# ae302f.net
KiCad netlist of a schematic drawn in Altium Designer
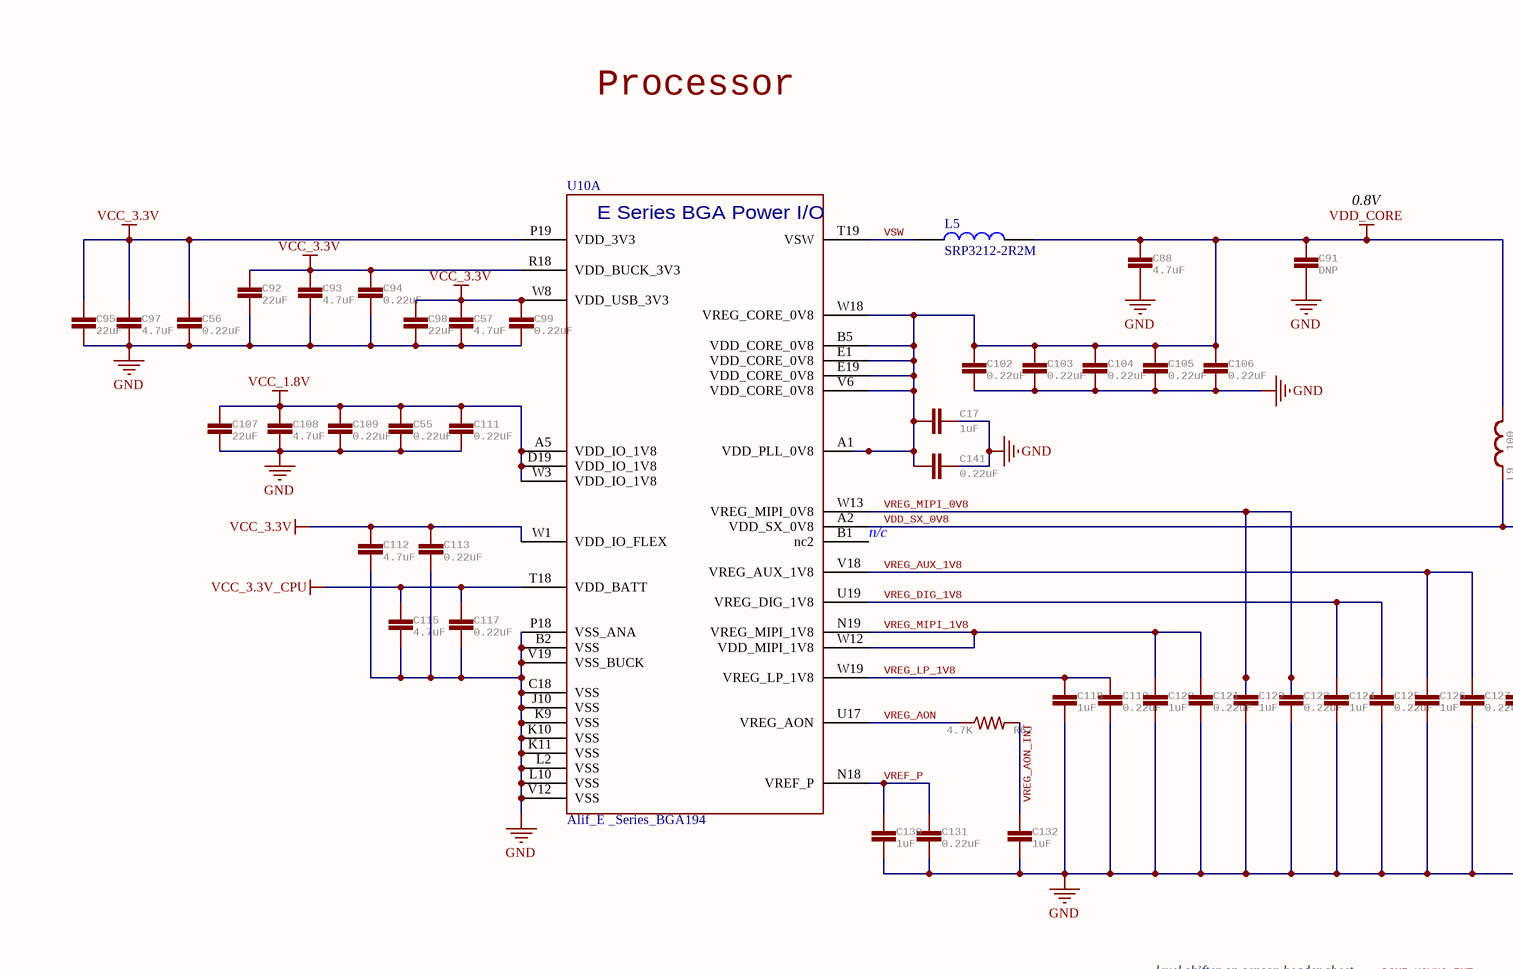
[diagram p0: ae302f.SchDoc, top left]
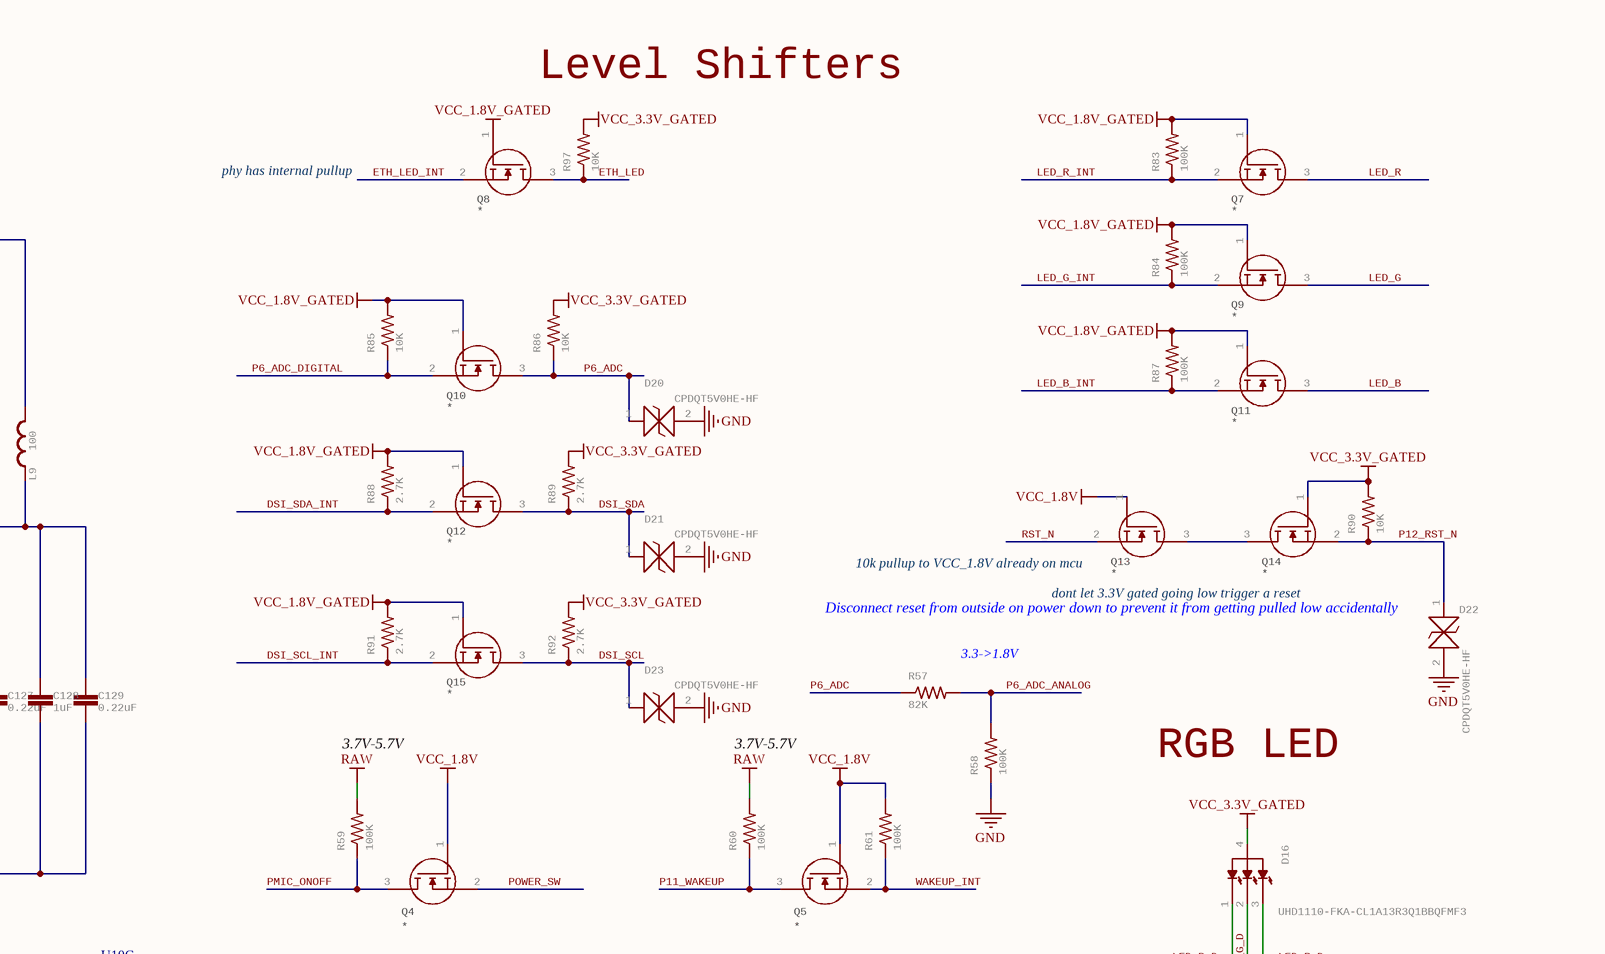
[diagram p1: ae302f.SchDoc, top right]
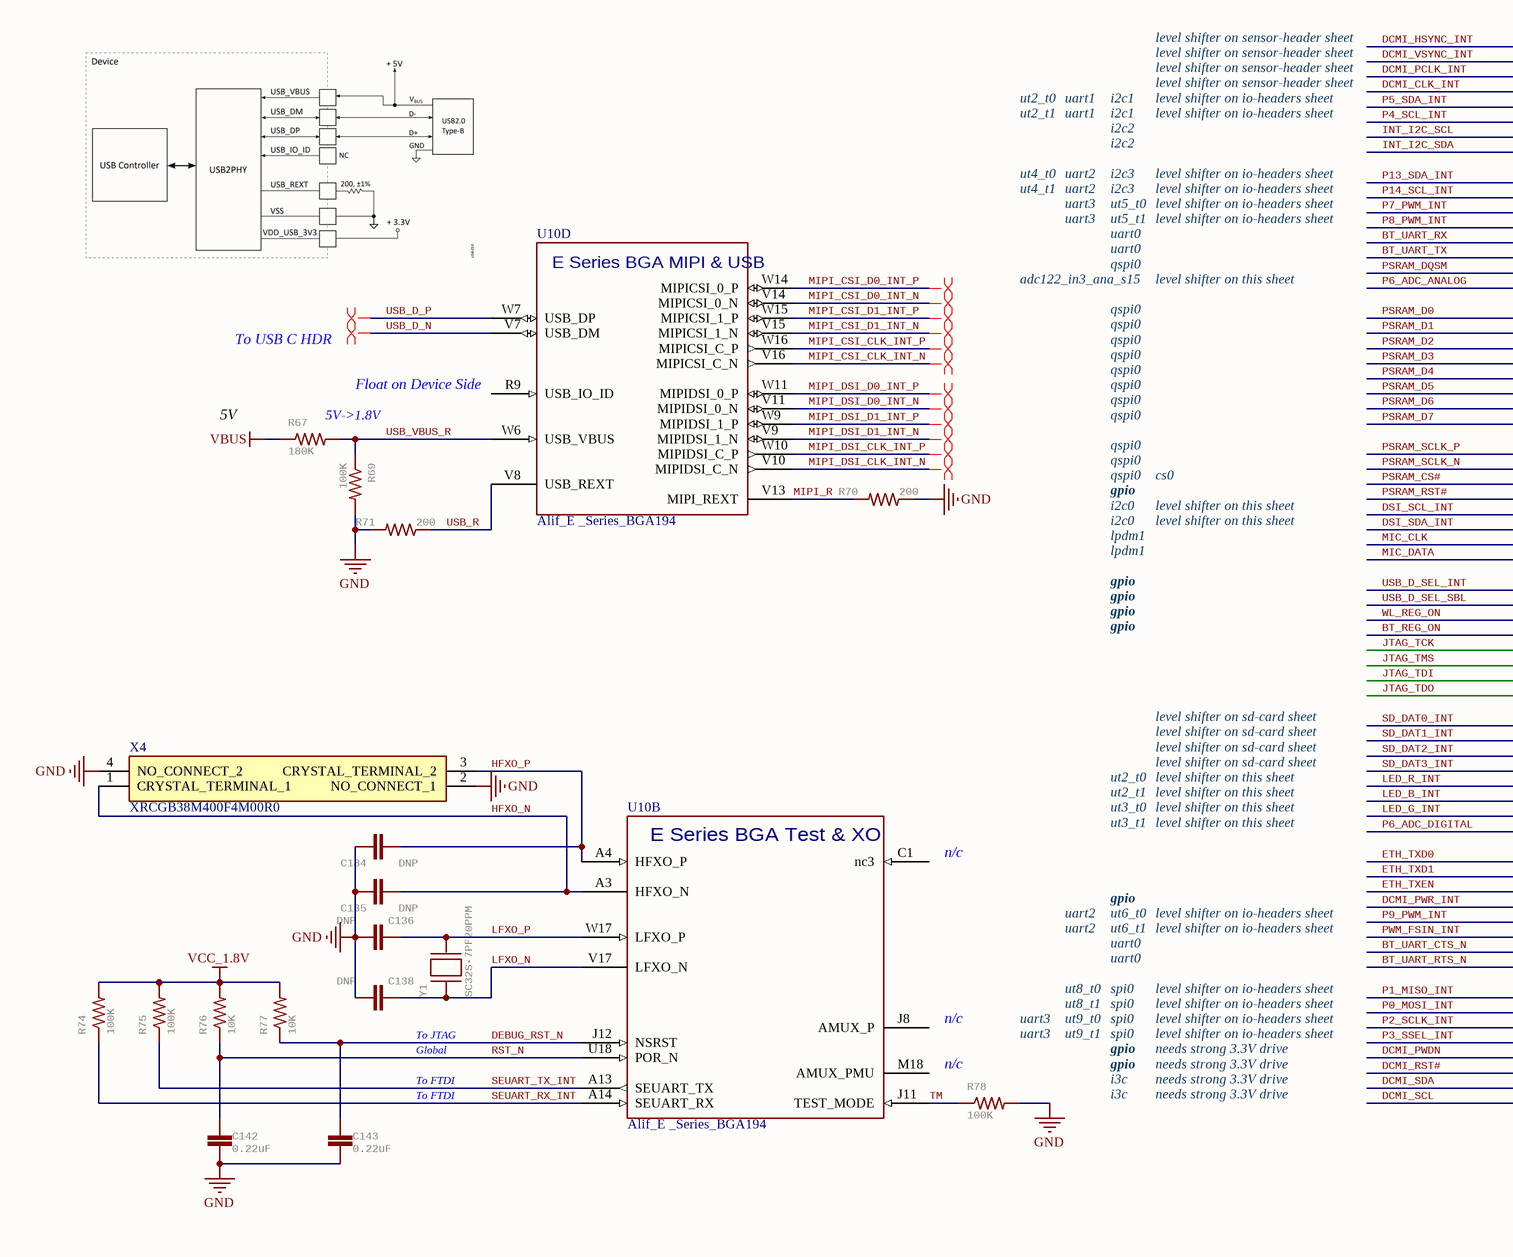
[diagram p2: ae302f.SchDoc, bottom left]
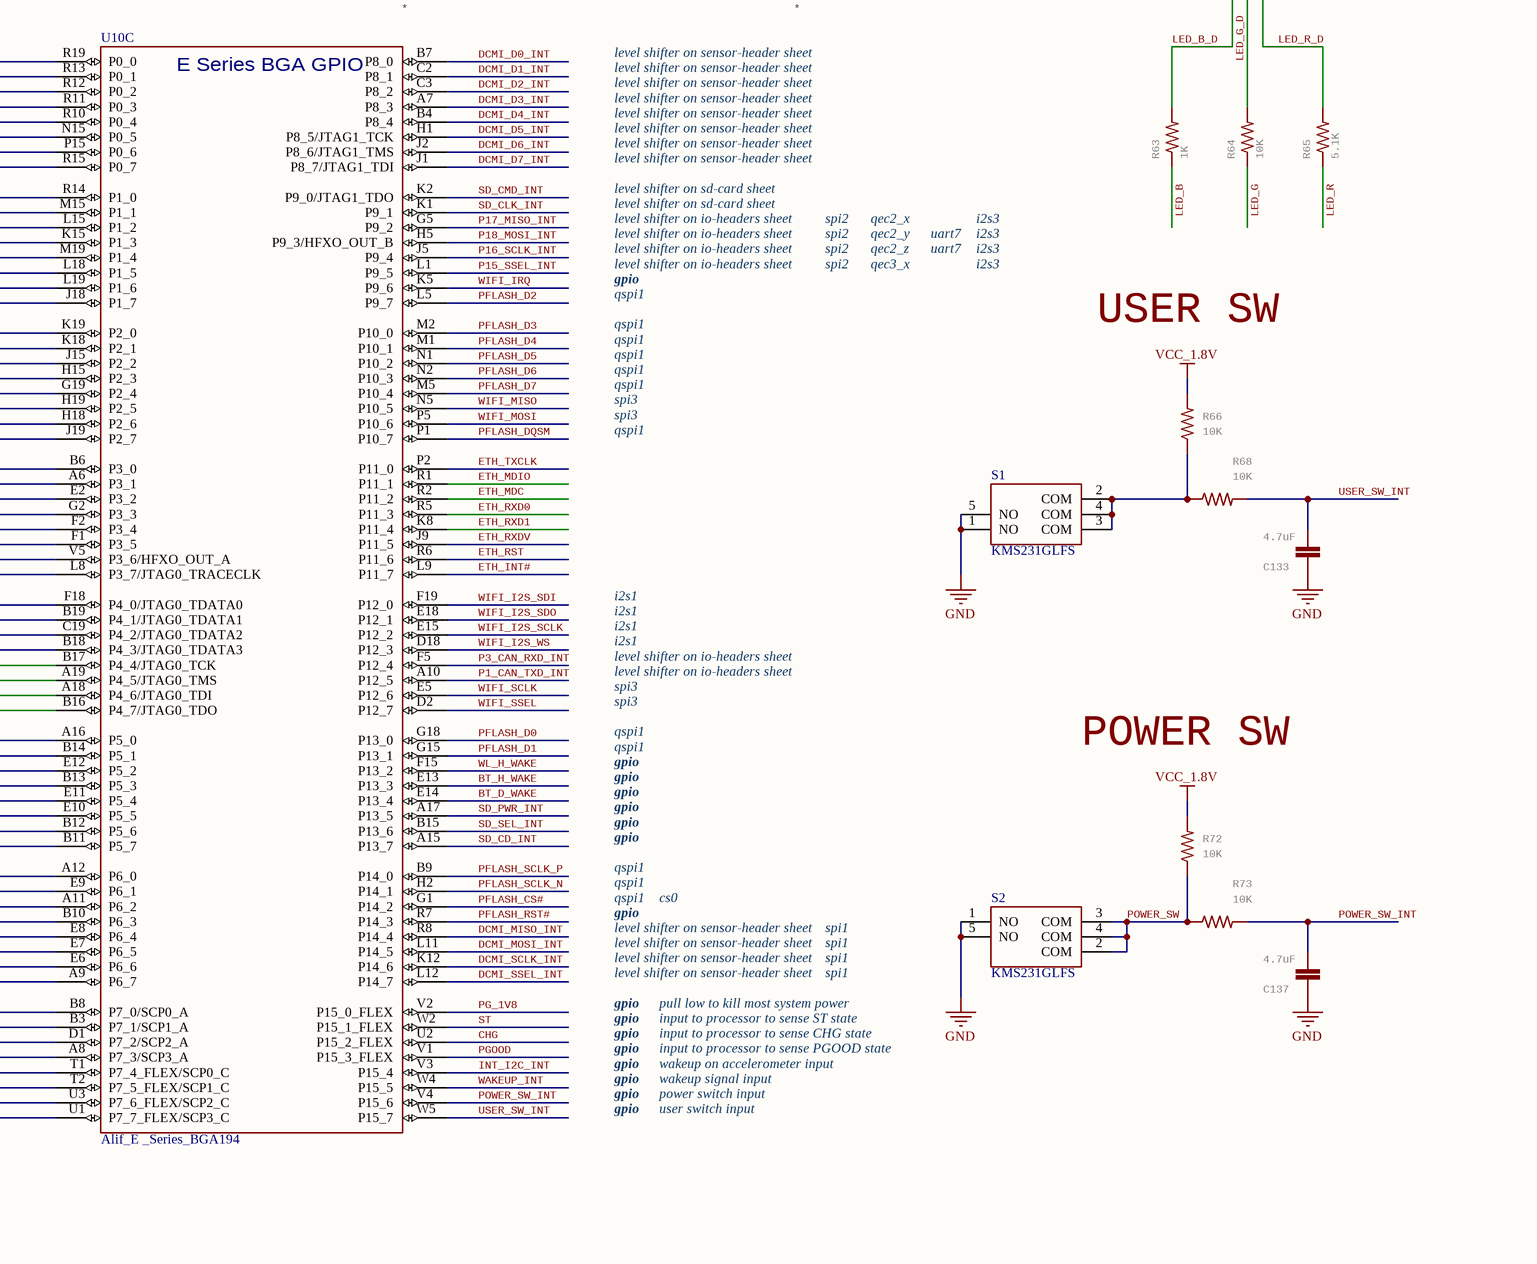
[diagram p3: ae302f.SchDoc, bottom right]

(export (version "E")
  (design (tool "Eeschema 10.0.6"))
  (components
    (comp (ref "C17")
      (value "1uF")
      (footprint "0402-CAP")
      (description "CapacitorStandard 0402 ceramic capacitor, and 0.1\" leaded capacitor.")
      (fields (field (name "MPN") "GRM155R61E105KA12J") (field (name "LIBRARYNAME") "sfe"))
      (libsource (lib "openmv-ae3") (part "CAP0402-CAP"))
    )
    (comp (ref "C55")
      (value "0.22uF")
      (footprint "C0201")
      (description "CAPACITOR, European symbol")
      (fields (field (name "MPN") "GRM033R60J224ME15D"))
      (libsource (lib "") (part "C-EUC0201_1"))
    )
    (comp (ref "C56")
      (value "0.22uF")
      (footprint "C0201")
      (description "CAPACITOR, European symbol")
      (fields (field (name "MPN") "GRM033R60J224ME15D"))
      (libsource (lib "") (part "C-EUC0201_1"))
    )
    (comp (ref "C57")
      (value "4.7uF")
      (footprint "0402-CAP")
      (description "CapacitorStandard 0603 ceramic capacitor, and 0.1\" leaded capacitor.")
      (fields (field (name "MPN") "JMK105BBJ475MV-F") (field (name "LIBRARYNAME") "sfe"))
      (libsource (lib "") (part "CAP0402-CAP_1"))
    )
    (comp (ref "C88")
      (value "4.7uF")
      (footprint "0402-CAP")
      (description "CapacitorStandard 0603 ceramic capacitor, and 0.1\" leaded capacitor.")
      (fields (field (name "MPN") "JMK105BBJ475MV-F") (field (name "LIBRARYNAME") "sfe"))
      (libsource (lib "") (part "CAP0402-CAP_1"))
    )
    (comp (ref "C91")
      (value "DNP")
      (footprint "0805")
      (libsource (lib "openmv-ae3") (part "22UF-0805-6.3V-20%"))
    )
    (comp (ref "C92")
      (value "22uF")
      (footprint "0805")
      (fields (field (name "MPN") "CL21A226MQQNNNE"))
      (libsource (lib "openmv-ae3") (part "22UF-0805-6.3V-20%"))
    )
    (comp (ref "C93")
      (value "4.7uF")
      (footprint "0402-CAP")
      (description "CapacitorStandard 0603 ceramic capacitor, and 0.1\" leaded capacitor.")
      (fields (field (name "MPN") "JMK105BBJ475MV-F") (field (name "LIBRARYNAME") "sfe"))
      (libsource (lib "") (part "CAP0402-CAP_1"))
    )
    (comp (ref "C94")
      (value "0.22uF")
      (footprint "C0201")
      (description "CAPACITOR, European symbol")
      (fields (field (name "MPN") "GRM033R60J224ME15D"))
      (libsource (lib "") (part "C-EUC0201_1"))
    )
    (comp (ref "C95")
      (value "22uF")
      (footprint "0805")
      (fields (field (name "MPN") "CL21A226MQQNNNE"))
      (libsource (lib "openmv-ae3") (part "22UF-0805-6.3V-20%"))
    )
    (comp (ref "C97")
      (value "4.7uF")
      (footprint "0402-CAP")
      (description "CapacitorStandard 0603 ceramic capacitor, and 0.1\" leaded capacitor.")
      (fields (field (name "MPN") "JMK105BBJ475MV-F") (field (name "LIBRARYNAME") "sfe"))
      (libsource (lib "") (part "CAP0402-CAP_1"))
    )
    (comp (ref "C98")
      (value "22uF")
      (footprint "0805")
      (fields (field (name "MPN") "CL21A226MQQNNNE"))
      (libsource (lib "openmv-ae3") (part "22UF-0805-6.3V-20%"))
    )
    (comp (ref "C99")
      (value "0.22uF")
      (footprint "C0201")
      (description "CAPACITOR, European symbol")
      (fields (field (name "MPN") "GRM033R60J224ME15D"))
      (libsource (lib "") (part "C-EUC0201_1"))
    )
    (comp (ref "C102")
      (value "0.22uF")
      (footprint "C0201")
      (description "CAPACITOR, European symbol")
      (fields (field (name "MPN") "GRM033R60J224ME15D"))
      (libsource (lib "") (part "C-EUC0201_1"))
    )
    (comp (ref "C103")
      (value "0.22uF")
      (footprint "C0201")
      (description "CAPACITOR, European symbol")
      (fields (field (name "MPN") "GRM033R60J224ME15D"))
      (libsource (lib "") (part "C-EUC0201_1"))
    )
    (comp (ref "C104")
      (value "0.22uF")
      (footprint "C0201")
      (description "CAPACITOR, European symbol")
      (fields (field (name "MPN") "GRM033R60J224ME15D"))
      (libsource (lib "") (part "C-EUC0201_1"))
    )
    (comp (ref "C105")
      (value "0.22uF")
      (footprint "C0201")
      (description "CAPACITOR, European symbol")
      (fields (field (name "MPN") "GRM033R60J224ME15D"))
      (libsource (lib "") (part "C-EUC0201_1"))
    )
    (comp (ref "C106")
      (value "0.22uF")
      (footprint "C0201")
      (description "CAPACITOR, European symbol")
      (fields (field (name "MPN") "GRM033R60J224ME15D"))
      (libsource (lib "") (part "C-EUC0201_1"))
    )
    (comp (ref "C107")
      (value "22uF")
      (footprint "0805")
      (fields (field (name "MPN") "CL21A226MQQNNNE"))
      (libsource (lib "openmv-ae3") (part "22UF-0805-6.3V-20%"))
    )
    (comp (ref "C108")
      (value "4.7uF")
      (footprint "0402-CAP")
      (description "CapacitorStandard 0603 ceramic capacitor, and 0.1\" leaded capacitor.")
      (fields (field (name "MPN") "JMK105BBJ475MV-F") (field (name "LIBRARYNAME") "sfe"))
      (libsource (lib "") (part "CAP0402-CAP_1"))
    )
    (comp (ref "C109")
      (value "0.22uF")
      (footprint "C0201")
      (description "CAPACITOR, European symbol")
      (fields (field (name "MPN") "GRM033R60J224ME15D"))
      (libsource (lib "") (part "C-EUC0201_1"))
    )
    (comp (ref "C111")
      (value "0.22uF")
      (footprint "C0201")
      (description "CAPACITOR, European symbol")
      (fields (field (name "MPN") "GRM033R60J224ME15D"))
      (libsource (lib "") (part "C-EUC0201_1"))
    )
    (comp (ref "C112")
      (value "4.7uF")
      (footprint "0402-CAP")
      (description "CapacitorStandard 0603 ceramic capacitor, and 0.1\" leaded capacitor.")
      (fields (field (name "MPN") "JMK105BBJ475MV-F") (field (name "LIBRARYNAME") "sfe"))
      (libsource (lib "") (part "CAP0402-CAP_1"))
    )
    (comp (ref "C113")
      (value "0.22uF")
      (footprint "C0201")
      (description "CAPACITOR, European symbol")
      (fields (field (name "MPN") "GRM033R60J224ME15D"))
      (libsource (lib "") (part "C-EUC0201_1"))
    )
    (comp (ref "C115")
      (value "4.7uF")
      (footprint "0402-CAP")
      (description "CapacitorStandard 0603 ceramic capacitor, and 0.1\" leaded capacitor.")
      (fields (field (name "MPN") "JMK105BBJ475MV-F") (field (name "LIBRARYNAME") "sfe"))
      (libsource (lib "") (part "CAP0402-CAP_1"))
    )
    (comp (ref "C117")
      (value "0.22uF")
      (footprint "C0201")
      (description "CAPACITOR, European symbol")
      (fields (field (name "MPN") "GRM033R60J224ME15D"))
      (libsource (lib "") (part "C-EUC0201_1"))
    )
    (comp (ref "C118")
      (value "1uF")
      (footprint "0402-CAP")
      (description "CapacitorStandard 0402 ceramic capacitor, and 0.1\" leaded capacitor.")
      (fields (field (name "MPN") "GRM155R61E105KA12J") (field (name "LIBRARYNAME") "sfe"))
      (libsource (lib "") (part "CAP0402-CAP_1"))
    )
    (comp (ref "C119")
      (value "0.22uF")
      (footprint "C0201")
      (description "CAPACITOR, European symbol")
      (fields (field (name "MPN") "GRM033R60J224ME15D"))
      (libsource (lib "") (part "C-EUC0201_1"))
    )
    (comp (ref "C120")
      (value "1uF")
      (footprint "0402-CAP")
      (description "CapacitorStandard 0402 ceramic capacitor, and 0.1\" leaded capacitor.")
      (fields (field (name "MPN") "GRM155R61E105KA12J") (field (name "LIBRARYNAME") "sfe"))
      (libsource (lib "") (part "CAP0402-CAP_1"))
    )
    (comp (ref "C121")
      (value "0.22uF")
      (footprint "C0201")
      (description "CAPACITOR, European symbol")
      (fields (field (name "MPN") "GRM033R60J224ME15D"))
      (libsource (lib "") (part "C-EUC0201_1"))
    )
    (comp (ref "C122")
      (value "1uF")
      (footprint "0402-CAP")
      (description "CapacitorStandard 0402 ceramic capacitor, and 0.1\" leaded capacitor.")
      (fields (field (name "MPN") "GRM155R61E105KA12J") (field (name "LIBRARYNAME") "sfe"))
      (libsource (lib "") (part "CAP0402-CAP_1"))
    )
    (comp (ref "C123")
      (value "0.22uF")
      (footprint "C0201")
      (description "CAPACITOR, European symbol")
      (fields (field (name "MPN") "GRM033R60J224ME15D"))
      (libsource (lib "") (part "C-EUC0201_1"))
    )
    (comp (ref "C124")
      (value "1uF")
      (footprint "0402-CAP")
      (description "CapacitorStandard 0402 ceramic capacitor, and 0.1\" leaded capacitor.")
      (fields (field (name "MPN") "GRM155R61E105KA12J") (field (name "LIBRARYNAME") "sfe"))
      (libsource (lib "") (part "CAP0402-CAP_1"))
    )
    (comp (ref "C125")
      (value "0.22uF")
      (footprint "C0201")
      (description "CAPACITOR, European symbol")
      (fields (field (name "MPN") "GRM033R60J224ME15D"))
      (libsource (lib "") (part "C-EUC0201_1"))
    )
    (comp (ref "C126")
      (value "1uF")
      (footprint "0402-CAP")
      (description "CapacitorStandard 0402 ceramic capacitor, and 0.1\" leaded capacitor.")
      (fields (field (name "MPN") "GRM155R61E105KA12J") (field (name "LIBRARYNAME") "sfe"))
      (libsource (lib "") (part "CAP0402-CAP_1"))
    )
    (comp (ref "C127")
      (value "0.22uF")
      (footprint "C0201")
      (description "CAPACITOR, European symbol")
      (fields (field (name "MPN") "GRM033R60J224ME15D"))
      (libsource (lib "") (part "C-EUC0201_2"))
    )
    (comp (ref "C128")
      (value "1uF")
      (footprint "0402-CAP")
      (description "CapacitorStandard 0402 ceramic capacitor, and 0.1\" leaded capacitor.")
      (fields (field (name "MPN") "GRM155R61E105KA12J") (field (name "LIBRARYNAME") "sfe"))
      (libsource (lib "") (part "CAP0402-CAP_1"))
    )
    (comp (ref "C129")
      (value "0.22uF")
      (footprint "C0201")
      (description "CAPACITOR, European symbol")
      (fields (field (name "MPN") "GRM033R60J224ME15D"))
      (libsource (lib "") (part "C-EUC0201_1"))
    )
    (comp (ref "C130")
      (value "1uF")
      (footprint "0402-CAP")
      (description "CapacitorStandard 0402 ceramic capacitor, and 0.1\" leaded capacitor.")
      (fields (field (name "MPN") "GRM155R61E105KA12J") (field (name "LIBRARYNAME") "sfe"))
      (libsource (lib "") (part "CAP0402-CAP_1"))
    )
    (comp (ref "C131")
      (value "0.22uF")
      (footprint "C0201")
      (description "CAPACITOR, European symbol")
      (fields (field (name "MPN") "GRM033R60J224ME15D"))
      (libsource (lib "") (part "C-EUC0201_1"))
    )
    (comp (ref "C132")
      (value "1uF")
      (footprint "0402-CAP")
      (description "CapacitorStandard 0402 ceramic capacitor, and 0.1\" leaded capacitor.")
      (fields (field (name "MPN") "GRM155R61E105KA12J") (field (name "LIBRARYNAME") "sfe"))
      (libsource (lib "") (part "CAP0402-CAP_1"))
    )
    (comp (ref "C133")
      (value "4.7uF")
      (footprint "0402-CAP")
      (description "CapacitorStandard 0603 ceramic capacitor, and 0.1\" leaded capacitor.")
      (fields (field (name "MPN") "JMK105BBJ475MV-F") (field (name "LIBRARYNAME") "sfe"))
      (libsource (lib "") (part "CAP0402-CAP_2"))
    )
    (comp (ref "C134")
      (value "DNP")
      (footprint "C0201")
      (description "CAPACITOR, European symbol")
      (libsource (lib "openmv-ae3") (part "C-EUC0201"))
    )
    (comp (ref "C135")
      (value "DNP")
      (footprint "C0201")
      (description "CAPACITOR, European symbol")
      (libsource (lib "openmv-ae3") (part "C-EUC0201"))
    )
    (comp (ref "C136")
      (value "DNP")
      (footprint "C0201")
      (description "CAPACITOR, European symbol")
      (libsource (lib "") (part "C-EUC0201_3"))
    )
    (comp (ref "C137")
      (value "4.7uF")
      (footprint "0402-CAP")
      (description "CapacitorStandard 0603 ceramic capacitor, and 0.1\" leaded capacitor.")
      (fields (field (name "MPN") "JMK105BBJ475MV-F") (field (name "LIBRARYNAME") "sfe"))
      (libsource (lib "") (part "CAP0402-CAP_2"))
    )
    (comp (ref "C138")
      (value "DNP")
      (footprint "C0201")
      (description "CAPACITOR, European symbol")
      (libsource (lib "") (part "C-EUC0201_3"))
    )
    (comp (ref "C141")
      (value "0.22uF")
      (footprint "C0201")
      (description "CAPACITOR, European symbol")
      (fields (field (name "MPN") "GRM033R60J224ME15D"))
      (libsource (lib "") (part "C-EUC0201_3"))
    )
    (comp (ref "C142")
      (value "0.22uF")
      (footprint "C0201")
      (description "CAPACITOR, European symbol")
      (fields (field (name "MPN") "GRM033R60J224ME15D"))
      (libsource (lib "") (part "C-EUC0201_1"))
    )
    (comp (ref "C143")
      (value "0.22uF")
      (footprint "C0201")
      (description "CAPACITOR, European symbol")
      (fields (field (name "MPN") "GRM033R60J224ME15D"))
      (libsource (lib "") (part "C-EUC0201_1"))
    )
    (comp (ref "D16")
      (value "UHD1110-FKA-CL1A13R3Q1BBQFMF3")
      (footprint "LED_UHD1110-FKA-CL1A13R3Q1BBQFMF3")
      (description "LED RGB SMD, SIZE 1 X 1 mm Check availability")
      (fields (field (name "MF") "Cree Inc.") (field (name "MPN") "UHD1110-FKA-CL1A13r3q1BBQFMF3"))
      (libsource (lib "openmv-ae3") (part "UHD1110-FKA-CL1A13R3Q1BBQFMF3"))
    )
    (comp (ref "D20")
      (value "CPDQT5V0HE-HF")
      (footprint "CPDQT5V0HEHF")
      (description "ESD Suppressors / TVS Diodes DIODE ESD 5VWM 65W 0402/SOD-923F   Source:  Datasheet")
      (fields (field (name "MOUSER_PART_NUMBER") "MOUSER_PART_NUMBER"))
      (libsource (lib "openmv-ae3") (part "CPDQT5V0HE-HF"))
    )
    (comp (ref "D21")
      (value "CPDQT5V0HE-HF")
      (footprint "CPDQT5V0HEHF")
      (description "ESD Suppressors / TVS Diodes DIODE ESD 5VWM 65W 0402/SOD-923F   Source:  Datasheet")
      (fields (field (name "MOUSER_PART_NUMBER") "MOUSER_PART_NUMBER"))
      (libsource (lib "openmv-ae3") (part "CPDQT5V0HE-HF"))
    )
    (comp (ref "D22")
      (value "CPDQT5V0HE-HF")
      (footprint "CPDQT5V0HEHF")
      (description "ESD Suppressors / TVS Diodes DIODE ESD 5VWM 65W 0402/SOD-923F   Source:  Datasheet")
      (fields (field (name "MOUSER_PART_NUMBER") "MOUSER_PART_NUMBER"))
      (libsource (lib "openmv-ae3") (part "CPDQT5V0HE-HF"))
    )
    (comp (ref "D23")
      (value "CPDQT5V0HE-HF")
      (footprint "CPDQT5V0HEHF")
      (description "ESD Suppressors / TVS Diodes DIODE ESD 5VWM 65W 0402/SOD-923F   Source:  Datasheet")
      (fields (field (name "MOUSER_PART_NUMBER") "MOUSER_PART_NUMBER"))
      (libsource (lib "openmv-ae3") (part "CPDQT5V0HE-HF"))
    )
    (comp (ref "L5")
      (value "SRP3212-2R2M")
      (footprint "IND3225X100N")
      (description "Ind,3.2x2.5x1mm,2.2uH?20%,4A,shd")
      (fields (field (name "MOUSER PART NUMBER") "652-SRP3212-2R2M"))
      (libsource (lib "openmv-ae3") (part "SRP3212-2R2M"))
    )
    (comp (ref "L9")
      (value "100")
      (footprint "C0402")
      (fields (field (name "MPN") "MFBM1V1005-101-R") (field (name "LIBRARYNAME") "sfe"))
      (libsource (lib "openmv-ae3") (part "INDUCTOR0402"))
    )
    (comp (ref "Q4")
      (value "NMOS")
      (footprint "DFN1006")
      (fields (field (name "MPN") "*"))
      (libsource (lib "openmv-ae3") (part "NMOS"))
    )
    (comp (ref "Q5")
      (value "NMOS")
      (footprint "DFN1006")
      (fields (field (name "MPN") "*"))
      (libsource (lib "openmv-ae3") (part "NMOS"))
    )
    (comp (ref "Q7")
      (value "NMOS")
      (footprint "DFN1006")
      (fields (field (name "MPN") "*"))
      (libsource (lib "openmv-ae3") (part "NMOS"))
    )
    (comp (ref "Q8")
      (value "NMOS")
      (footprint "DFN1006")
      (fields (field (name "MPN") "*"))
      (libsource (lib "openmv-ae3") (part "NMOS"))
    )
    (comp (ref "Q9")
      (value "NMOS")
      (footprint "DFN1006")
      (fields (field (name "MPN") "*"))
      (libsource (lib "openmv-ae3") (part "NMOS"))
    )
    (comp (ref "Q10")
      (value "NMOS")
      (footprint "DFN1006")
      (fields (field (name "MPN") "*"))
      (libsource (lib "openmv-ae3") (part "NMOS"))
    )
    (comp (ref "Q11")
      (value "NMOS")
      (footprint "DFN1006")
      (fields (field (name "MPN") "*"))
      (libsource (lib "openmv-ae3") (part "NMOS"))
    )
    (comp (ref "Q12")
      (value "NMOS")
      (footprint "DFN1006")
      (fields (field (name "MPN") "*"))
      (libsource (lib "openmv-ae3") (part "NMOS"))
    )
    (comp (ref "Q13")
      (value "NMOS")
      (footprint "DFN1006")
      (fields (field (name "MPN") "*"))
      (libsource (lib "openmv-ae3") (part "NMOS"))
    )
    (comp (ref "Q14")
      (value "NMOS")
      (footprint "DFN1006")
      (fields (field (name "MPN") "*"))
      (libsource (lib "openmv-ae3") (part "NMOS"))
    )
    (comp (ref "Q15")
      (value "NMOS")
      (footprint "DFN1006")
      (fields (field (name "MPN") "*"))
      (libsource (lib "openmv-ae3") (part "NMOS"))
    )
    (comp (ref "R57")
      (value "82K")
      (footprint "R0201")
      (fields (field (name "LIBRARYNAME") "sfe"))
      (libsource (lib "openmv-ae3") (part "RESISTOR0402-RES"))
    )
    (comp (ref "R58")
      (value "100K")
      (footprint "R0201")
      (fields (field (name "LIBRARYNAME") "sfe"))
      (libsource (lib "openmv-ae3") (part "RESISTOR0402-RES"))
    )
    (comp (ref "R59")
      (value "100K")
      (footprint "0402-RES")
      (description "ResistorBasic schematic elements and footprints for 0603, 1206, and PTH resistors.")
      (fields (field (name "MPN") "AC0402FR-07100KL") (field (name "LIBRARYNAME") "sfe"))
      (libsource (lib "openmv-ae3") (part "RESISTOR0402-RES"))
    )
    (comp (ref "R60")
      (value "100K")
      (footprint "R0201")
      (fields (field (name "LIBRARYNAME") "sfe"))
      (libsource (lib "openmv-ae3") (part "RESISTOR0402-RES"))
    )
    (comp (ref "R61")
      (value "100K")
      (footprint "R0201")
      (fields (field (name "LIBRARYNAME") "sfe"))
      (libsource (lib "openmv-ae3") (part "RESISTOR0402-RES"))
    )
    (comp (ref "R62")
      (value "4.7K")
      (footprint "0402-RES")
      (description "ResistorBasic schematic elements and footprints for 0603, 1206, and PTH resistors.")
      (fields (field (name "MPN") "RT0402FRE074K7L") (field (name "LIBRARYNAME") "sfe"))
      (libsource (lib "openmv-ae3") (part "RESISTOR0402-RES"))
    )
    (comp (ref "R63")
      (value "1K")
      (footprint "R0201")
      (description "ResistorBasic schematic elements and footprints for 0603, 1206, and PTH resistors.")
      (fields (field (name "LIBRARYNAME") "sfe"))
      (libsource (lib "openmv-ae3") (part "RESISTOR0402-RES"))
    )
    (comp (ref "R64")
      (value "10K")
      (footprint "R0201")
      (description "ResistorBasic schematic elements and footprints for 0603, 1206, and PTH resistors.")
      (fields (field (name "LIBRARYNAME") "sfe"))
      (libsource (lib "openmv-ae3") (part "RESISTOR0402-RES"))
    )
    (comp (ref "R65")
      (value "5.1K")
      (footprint "R0201")
      (description "ResistorBasic schematic elements and footprints for 0603, 1206, and PTH resistors.")
      (fields (field (name "LIBRARYNAME") "sfe"))
      (libsource (lib "openmv-ae3") (part "RESISTOR0402-RES"))
    )
    (comp (ref "R66")
      (value "10K")
      (footprint "0402-RES")
      (description "ResistorBasic schematic elements and footprints for 0603, 1206, and PTH resistors.")
      (fields (field (name "MPN") "AC0402FR-1310K") (field (name "LIBRARYNAME") "sfe"))
      (libsource (lib "openmv-ae3") (part "RESISTOR0402-RES"))
    )
    (comp (ref "R67")
      (value "180K")
      (footprint "R0201")
      (fields (field (name "LIBRARYNAME") "sfe"))
      (libsource (lib "openmv-ae3") (part "RESISTOR0402-RES"))
    )
    (comp (ref "R68")
      (value "10K")
      (footprint "0402-RES")
      (description "ResistorBasic schematic elements and footprints for 0603, 1206, and PTH resistors.")
      (fields (field (name "MPN") "AC0402FR-1310K") (field (name "LIBRARYNAME") "sfe"))
      (libsource (lib "openmv-ae3") (part "RESISTOR0402-RES"))
    )
    (comp (ref "R69")
      (value "100K")
      (footprint "R0201")
      (fields (field (name "LIBRARYNAME") "sfe"))
      (libsource (lib "openmv-ae3") (part "RESISTOR0402-RES"))
    )
    (comp (ref "R70")
      (value "200")
      (footprint "R0201")
      (fields (field (name "LIBRARYNAME") "sfe"))
      (libsource (lib "openmv-ae3") (part "RESISTOR0402-RES"))
    )
    (comp (ref "R71")
      (value "200")
      (footprint "R0201")
      (fields (field (name "LIBRARYNAME") "sfe"))
      (libsource (lib "openmv-ae3") (part "RESISTOR0402-RES"))
    )
    (comp (ref "R72")
      (value "10K")
      (footprint "0402-RES")
      (description "ResistorBasic schematic elements and footprints for 0603, 1206, and PTH resistors.")
      (fields (field (name "MPN") "AC0402FR-1310K") (field (name "LIBRARYNAME") "sfe"))
      (libsource (lib "openmv-ae3") (part "RESISTOR0402-RES"))
    )
    (comp (ref "R73")
      (value "10K")
      (footprint "0402-RES")
      (description "ResistorBasic schematic elements and footprints for 0603, 1206, and PTH resistors.")
      (fields (field (name "MPN") "AC0402FR-1310K") (field (name "LIBRARYNAME") "sfe"))
      (libsource (lib "openmv-ae3") (part "RESISTOR0402-RES"))
    )
    (comp (ref "R74")
      (value "100K")
      (footprint "R0201")
      (fields (field (name "LIBRARYNAME") "sfe"))
      (libsource (lib "openmv-ae3") (part "RESISTOR0402-RES"))
    )
    (comp (ref "R75")
      (value "100K")
      (footprint "R0201")
      (fields (field (name "LIBRARYNAME") "sfe"))
      (libsource (lib "openmv-ae3") (part "RESISTOR0402-RES"))
    )
    (comp (ref "R76")
      (value "10K")
      (footprint "R0201")
      (fields (field (name "LIBRARYNAME") "sfe"))
      (libsource (lib "openmv-ae3") (part "RESISTOR0402-RES"))
    )
    (comp (ref "R77")
      (value "10K")
      (footprint "R0201")
      (fields (field (name "LIBRARYNAME") "sfe"))
      (libsource (lib "openmv-ae3") (part "RESISTOR0402-RES"))
    )
    (comp (ref "R78")
      (value "100K")
      (footprint "r0201")
      (fields (field (name "LIBRARYNAME") "sfe"))
      (libsource (lib "openmv-ae3") (part "RESISTOR0402-RES"))
    )
    (comp (ref "R83")
      (value "100K")
      (footprint "R0201")
      (fields (field (name "LIBRARYNAME") "sfe"))
      (libsource (lib "openmv-ae3") (part "RESISTOR0402-RES"))
    )
    (comp (ref "R84")
      (value "100K")
      (footprint "R0201")
      (fields (field (name "LIBRARYNAME") "sfe"))
      (libsource (lib "openmv-ae3") (part "RESISTOR0402-RES"))
    )
    (comp (ref "R85")
      (value "10K")
      (footprint "R0201")
      (description "ResistorBasic schematic elements and footprints for 0603, 1206, and PTH resistors.")
      (fields (field (name "LIBRARYNAME") "sfe"))
      (libsource (lib "openmv-ae3") (part "RESISTOR0402-RES"))
    )
    (comp (ref "R86")
      (value "10K")
      (footprint "R0201")
      (description "ResistorBasic schematic elements and footprints for 0603, 1206, and PTH resistors.")
      (fields (field (name "LIBRARYNAME") "sfe"))
      (libsource (lib "openmv-ae3") (part "RESISTOR0402-RES"))
    )
    (comp (ref "R87")
      (value "100K")
      (footprint "R0201")
      (fields (field (name "LIBRARYNAME") "sfe"))
      (libsource (lib "openmv-ae3") (part "RESISTOR0402-RES"))
    )
    (comp (ref "R88")
      (value "2.7K")
      (footprint "R0201")
      (fields (field (name "LIBRARYNAME") "sfe"))
      (libsource (lib "openmv-ae3") (part "RESISTOR0402-RES"))
    )
    (comp (ref "R89")
      (value "2.7K")
      (footprint "R0201")
      (fields (field (name "LIBRARYNAME") "sfe"))
      (libsource (lib "openmv-ae3") (part "RESISTOR0402-RES"))
    )
    (comp (ref "R90")
      (value "10K")
      (footprint "R0201")
      (description "ResistorBasic schematic elements and footprints for 0603, 1206, and PTH resistors.")
      (fields (field (name "LIBRARYNAME") "sfe"))
      (libsource (lib "openmv-ae3") (part "RESISTOR0402-RES"))
    )
    (comp (ref "R91")
      (value "2.7K")
      (footprint "R0201")
      (fields (field (name "LIBRARYNAME") "sfe"))
      (libsource (lib "openmv-ae3") (part "RESISTOR0402-RES"))
    )
    (comp (ref "R92")
      (value "2.7K")
      (footprint "R0201")
      (fields (field (name "LIBRARYNAME") "sfe"))
      (libsource (lib "openmv-ae3") (part "RESISTOR0402-RES"))
    )
    (comp (ref "R97")
      (value "10K")
      (footprint "R0201")
      (description "ResistorBasic schematic elements and footprints for 0603, 1206, and PTH resistors.")
      (fields (field (name "LIBRARYNAME") "sfe"))
      (libsource (lib "openmv-ae3") (part "RESISTOR0402-RES"))
    )
    (comp (ref "S1") (value "KMS231GLFS") (footprint "KMS231GLFS") (libsource (lib "") (part "KMS231GLFS_1")))
    (comp (ref "S2")
      (value "KMS231GLFS")
      (footprint "KMS231GLFS")
      (libsource (lib "openmv-ae3") (part "KMS231GLFS"))
    )
    (comp (ref "U10")
      (value "Alif_E _Series_BGA194")
      (footprint "BGA194 _CENTERED")
      (description "IC,Alif E7 MCU, Rev B silicon,BGA194")
      (fields (field (name "PART NUMBER") "AE302F80F55D5LE"))
      (libsource (lib "openmv-ae3") (part "E7_Bx_BGA_194_noGNSS"))
    )
    (comp (ref "X4")
      (value "XRCGB38M400F4M00R0")
      (footprint "XTAL_2016")
      (description "2.0X1.6X0.65MM 38.4MHZ CRYSTAL")
      (libsource (lib "openmv-ae3") (part "XRCGB38M400F4M00R0"))
    )
    (comp (ref "Y1")
      (value "SC32S-7PF20PPM")
      (footprint "XTAL_ABS07-32.768KHZ-7-T")
      (description "Check availability")
      (fields (field (name "MF") "Abracon") (field (name "MP") "ABS07-32.768KHZ-7-T"))
      (libsource (lib "openmv-ae3") (part "ABS07-32.768KHZ-7-T"))
    )
  )
  (nets
    (net (code "1") (name "/BT_D_WAKE") (class "Default")
      (node (ref "U10") (pin "E14") (pinfunction "P13_4_E14") (pintype "bidirectional"))
    )
    (net (code "2") (name "/BT_H_WAKE") (class "Default")
      (node (ref "U10") (pin "E13") (pinfunction "P13_3_E13") (pintype "bidirectional"))
    )
    (net (code "3") (name "/BT_REG_ON") (class "Default")
      (node (ref "U10") (pin "B18") (pinfunction "P4_3/JTAG0_TDATA3_B18") (pintype "bidirectional"))
    )
    (net (code "4") (name "/BT_UART_CTS_N") (class "Default")
      (node (ref "U10") (pin "E6") (pinfunction "P6_6_E6") (pintype "bidirectional"))
    )
    (net (code "5") (name "/BT_UART_RTS_N") (class "Default")
      (node (ref "U10") (pin "A9") (pinfunction "P6_7_A9") (pintype "bidirectional"))
    )
    (net (code "6") (name "/BT_UART_RX") (class "Default")
      (node (ref "U10") (pin "M19") (pinfunction "P1_4_M19") (pintype "bidirectional"))
    )
    (net (code "7") (name "/BT_UART_TX") (class "Default")
      (node (ref "U10") (pin "L18") (pinfunction "P1_5_L18") (pintype "bidirectional"))
    )
    (net (code "8") (name "/CHG") (class "Default")
      (node (ref "U10") (pin "U2") (pinfunction "P15_2_FLEX_U2") (pintype "bidirectional"))
    )
    (net (code "9") (name "/DCMI_CLK_INT") (class "Default")
      (node (ref "U10") (pin "R11") (pinfunction "P0_3_R11") (pintype "bidirectional"))
    )
    (net (code "10") (name "/DCMI_D0_INT") (class "Default")
      (node (ref "U10") (pin "B7") (pinfunction "P8_0_B7") (pintype "bidirectional"))
    )
    (net (code "11") (name "/DCMI_D1_INT") (class "Default")
      (node (ref "U10") (pin "C2") (pinfunction "P8_1_C2") (pintype "bidirectional"))
    )
    (net (code "12") (name "/DCMI_D2_INT") (class "Default")
      (node (ref "U10") (pin "C3") (pinfunction "P8_2_C3") (pintype "bidirectional"))
    )
    (net (code "13") (name "/DCMI_D3_INT") (class "Default")
      (node (ref "U10") (pin "A7") (pinfunction "P8_3_A7") (pintype "bidirectional"))
    )
    (net (code "14") (name "/DCMI_D4_INT") (class "Default")
      (node (ref "U10") (pin "B4") (pinfunction "P8_4_B4") (pintype "bidirectional"))
    )
    (net (code "15") (name "/DCMI_D5_INT") (class "Default")
      (node (ref "U10") (pin "H1") (pinfunction "P8_5/JTAG1_TCK_H1") (pintype "bidirectional"))
    )
    (net (code "16") (name "/DCMI_D6_INT") (class "Default")
      (node (ref "U10") (pin "J2") (pinfunction "P8_6/JTAG1_TMS_J2") (pintype "bidirectional"))
    )
    (net (code "17") (name "/DCMI_D7_INT") (class "Default")
      (node (ref "U10") (pin "J1") (pinfunction "P8_7/JTAG1_TDI_J1") (pintype "bidirectional"))
    )
    (net (code "18") (name "/DCMI_HSYNC_INT") (class "Default")
      (node (ref "U10") (pin "R19") (pinfunction "P0_0_R19") (pintype "bidirectional"))
    )
    (net (code "19") (name "/DCMI_MISO_INT") (class "Default")
      (node (ref "U10") (pin "R8") (pinfunction "P14_4_R8") (pintype "bidirectional"))
    )
    (net (code "20") (name "/DCMI_MOSI_INT") (class "Default")
      (node (ref "U10") (pin "L11") (pinfunction "P14_5_L11") (pintype "bidirectional"))
    )
    (net (code "21") (name "/DCMI_PCLK_INT") (class "Default")
      (node (ref "U10") (pin "R12") (pinfunction "P0_2_R12") (pintype "bidirectional"))
    )
    (net (code "22") (name "/DCMI_PWDN") (class "Default")
      (node (ref "U10") (pin "T1") (pinfunction "P7_4_FLEX/SCP0_C_T1") (pintype "bidirectional"))
    )
    (net (code "23") (name "/DCMI_PWR_INT") (class "Default")
      (node (ref "U10") (pin "B10") (pinfunction "P6_3_B10") (pintype "bidirectional"))
    )
    (net (code "24") (name "/DCMI_RST#") (class "Default")
      (node (ref "U10") (pin "T2") (pinfunction "P7_5_FLEX/SCP1_C_T2") (pintype "bidirectional"))
    )
    (net (code "25") (name "/DCMI_SCL") (class "Default")
      (node (ref "U10") (pin "U1") (pinfunction "P7_7_FLEX/SCP3_C_U1") (pintype "bidirectional"))
    )
    (net (code "26") (name "/DCMI_SCLK_INT") (class "Default")
      (node (ref "U10") (pin "K12") (pinfunction "P14_6_K12") (pintype "bidirectional"))
    )
    (net (code "27") (name "/DCMI_SDA") (class "Default")
      (node (ref "U10") (pin "U3") (pinfunction "P7_6_FLEX/SCP2_C_U3") (pintype "bidirectional"))
    )
    (net (code "28") (name "/DCMI_SSEL_INT") (class "Default")
      (node (ref "U10") (pin "L12") (pinfunction "P14_7_L12") (pintype "bidirectional"))
    )
    (net (code "29") (name "/DCMI_VSYNC_INT") (class "Default")
      (node (ref "U10") (pin "R13") (pinfunction "P0_1_R13") (pintype "bidirectional"))
    )
    (net (code "30") (name "/DEBUG_RST_N") (class "Default")
      (node (ref "C143") (pin "2") (pinfunction "2_2") (pintype "passive"))
      (node (ref "R77") (pin "1") (pinfunction "1_1") (pintype "passive"))
      (node (ref "U10") (pin "J12") (pinfunction "NSRST_J12") (pintype "input"))
    )
    (net (code "31") (name "/DSI_SCL") (class "Default")
      (node (ref "D23") (pin "1") (pinfunction "1_1") (pintype "bidirectional"))
      (node (ref "Q15") (pin "3") (pinfunction "D_3") (pintype "bidirectional"))
      (node (ref "R92") (pin "1") (pinfunction "1_1") (pintype "passive"))
    )
    (net (code "32") (name "/DSI_SCL_INT") (class "Default")
      (node (ref "Q15") (pin "2") (pinfunction "S_2") (pintype "bidirectional"))
      (node (ref "R91") (pin "1") (pinfunction "1_1") (pintype "passive"))
      (node (ref "U10") (pin "F2") (pinfunction "P3_4_F2") (pintype "bidirectional"))
    )
    (net (code "33") (name "/DSI_SDA") (class "Default")
      (node (ref "D21") (pin "1") (pinfunction "1_1") (pintype "bidirectional"))
      (node (ref "Q12") (pin "3") (pinfunction "D_3") (pintype "bidirectional"))
      (node (ref "R89") (pin "1") (pinfunction "1_1") (pintype "passive"))
    )
    (net (code "34") (name "/DSI_SDA_INT") (class "Default")
      (node (ref "Q12") (pin "2") (pinfunction "S_2") (pintype "bidirectional"))
      (node (ref "R88") (pin "1") (pinfunction "1_1") (pintype "passive"))
      (node (ref "U10") (pin "F1") (pinfunction "P3_5_F1") (pintype "bidirectional"))
    )
    (net (code "35") (name "/ETH_INT#") (class "Default")
      (node (ref "U10") (pin "L9") (pinfunction "P11_7_L9") (pintype "bidirectional"))
    )
    (net (code "36") (name "/ETH_LED") (class "Default")
      (node (ref "Q8") (pin "3") (pinfunction "D_3") (pintype "bidirectional"))
      (node (ref "R97") (pin "1") (pinfunction "1_1") (pintype "passive"))
    )
    (net (code "37") (name "/ETH_LED_INT") (class "Default")
      (node (ref "Q8") (pin "2") (pinfunction "S_2") (pintype "bidirectional"))
    )
    (net (code "38") (name "/ETH_MDC") (class "Default")
      (node (ref "U10") (pin "R2") (pinfunction "P11_2_R2") (pintype "bidirectional"))
    )
    (net (code "39") (name "/ETH_MDIO") (class "Default")
      (node (ref "U10") (pin "R1") (pinfunction "P11_1_R1") (pintype "bidirectional"))
    )
    (net (code "40") (name "/ETH_RST") (class "Default")
      (node (ref "U10") (pin "R6") (pinfunction "P11_6_R6") (pintype "bidirectional"))
    )
    (net (code "41") (name "/ETH_RXD0") (class "Default")
      (node (ref "U10") (pin "R5") (pinfunction "P11_3_R5") (pintype "bidirectional"))
    )
    (net (code "42") (name "/ETH_RXD1") (class "Default")
      (node (ref "U10") (pin "K8") (pinfunction "P11_4_K8") (pintype "bidirectional"))
    )
    (net (code "43") (name "/ETH_RXDV") (class "Default")
      (node (ref "U10") (pin "J9") (pinfunction "P11_5_J9") (pintype "bidirectional"))
    )
    (net (code "44") (name "/ETH_TXCLK") (class "Default")
      (node (ref "U10") (pin "P2") (pinfunction "P11_0_P2") (pintype "bidirectional"))
    )
    (net (code "45") (name "/ETH_TXD0") (class "Default")
      (node (ref "U10") (pin "A12") (pinfunction "P6_0_A12") (pintype "bidirectional"))
    )
    (net (code "46") (name "/ETH_TXD1") (class "Default")
      (node (ref "U10") (pin "E9") (pinfunction "P6_1_E9") (pintype "bidirectional"))
    )
    (net (code "47") (name "/ETH_TXEN") (class "Default")
      (node (ref "U10") (pin "A11") (pinfunction "P6_2_A11") (pintype "bidirectional"))
    )
    (net (code "48") (name "/HFXO_N") (class "Default")
      (node (ref "C135") (pin "2") (pinfunction "2_2") (pintype "passive"))
      (node (ref "U10") (pin "A3") (pinfunction "HFXO_N_A3") (pintype "passive"))
      (node (ref "X4") (pin "1") (pinfunction "CRYSTAL_TERMINAL_1_1") (pintype "passive"))
    )
    (net (code "49") (name "/HFXO_P") (class "Default")
      (node (ref "C134") (pin "2") (pinfunction "2_2") (pintype "passive"))
      (node (ref "U10") (pin "A4") (pinfunction "HFXO_P_A4") (pintype "input"))
      (node (ref "X4") (pin "3") (pinfunction "CRYSTAL_TERMINAL_2_3") (pintype "passive"))
    )
    (net (code "50") (name "/INT_I2C_INT") (class "Default")
      (node (ref "U10") (pin "V3") (pinfunction "P15_4_V3") (pintype "bidirectional"))
    )
    (net (code "51") (name "/INT_I2C_SCL") (class "Default")
      (node (ref "U10") (pin "P15") (pinfunction "P0_6_P15") (pintype "bidirectional"))
    )
    (net (code "52") (name "/INT_I2C_SDA") (class "Default")
      (node (ref "U10") (pin "R15") (pinfunction "P0_7_R15") (pintype "bidirectional"))
    )
    (net (code "53") (name "/JTAG_TCK") (class "Default")
      (node (ref "U10") (pin "B17") (pinfunction "P4_4/JTAG0_TCK_B17") (pintype "bidirectional"))
    )
    (net (code "54") (name "/JTAG_TDI") (class "Default")
      (node (ref "U10") (pin "A18") (pinfunction "P4_6/JTAG0_TDI_A18") (pintype "bidirectional"))
    )
    (net (code "55") (name "/JTAG_TDO") (class "Default")
      (node (ref "U10") (pin "B16") (pinfunction "P4_7/JTAG0_TDO_B16") (pintype "bidirectional"))
    )
    (net (code "56") (name "/JTAG_TMS") (class "Default")
      (node (ref "U10") (pin "A19") (pinfunction "P4_5/JTAG0_TMS_A19") (pintype "bidirectional"))
    )
    (net (code "57") (name "/LED_B") (class "Default")
      (node (ref "Q11") (pin "3") (pinfunction "D_3") (pintype "bidirectional"))
      (node (ref "R63") (pin "1") (pinfunction "1_1") (pintype "passive"))
    )
    (net (code "58") (name "/LED_B_D") (class "Default")
      (node (ref "D16") (pin "1") (pinfunction "BLUE_1") (pintype "passive"))
      (node (ref "R63") (pin "2") (pinfunction "2_2") (pintype "passive"))
    )
    (net (code "59") (name "/LED_B_INT") (class "Default")
      (node (ref "Q11") (pin "2") (pinfunction "S_2") (pintype "bidirectional"))
      (node (ref "R87") (pin "1") (pinfunction "1_1") (pintype "passive"))
      (node (ref "U10") (pin "E10") (pinfunction "P5_5_E10") (pintype "bidirectional"))
    )
    (net (code "60") (name "/LED_G") (class "Default")
      (node (ref "Q9") (pin "3") (pinfunction "D_3") (pintype "bidirectional"))
      (node (ref "R64") (pin "1") (pinfunction "1_1") (pintype "passive"))
    )
    (net (code "61") (name "/LED_G_D") (class "Default")
      (node (ref "D16") (pin "2") (pinfunction "GREEN_2") (pintype "passive"))
      (node (ref "R64") (pin "2") (pinfunction "2_2") (pintype "passive"))
    )
    (net (code "62") (name "/LED_G_INT") (class "Default")
      (node (ref "Q9") (pin "2") (pinfunction "S_2") (pintype "bidirectional"))
      (node (ref "R84") (pin "1") (pinfunction "1_1") (pintype "passive"))
      (node (ref "U10") (pin "B12") (pinfunction "P5_6_B12") (pintype "bidirectional"))
    )
    (net (code "63") (name "/LED_R") (class "Default")
      (node (ref "Q7") (pin "3") (pinfunction "D_3") (pintype "bidirectional"))
      (node (ref "R65") (pin "1") (pinfunction "1_1") (pintype "passive"))
    )
    (net (code "64") (name "/LED_R_D") (class "Default")
      (node (ref "D16") (pin "3") (pinfunction "RED_3") (pintype "passive"))
      (node (ref "R65") (pin "2") (pinfunction "2_2") (pintype "passive"))
    )
    (net (code "65") (name "/LED_R_INT") (class "Default")
      (node (ref "Q7") (pin "2") (pinfunction "S_2") (pintype "bidirectional"))
      (node (ref "R83") (pin "1") (pinfunction "1_1") (pintype "passive"))
      (node (ref "U10") (pin "E11") (pinfunction "P5_4_E11") (pintype "bidirectional"))
    )
    (net (code "66") (name "/LFXO_N") (class "Default")
      (node (ref "C138") (pin "1") (pinfunction "1_1") (pintype "passive"))
      (node (ref "U10") (pin "V17") (pinfunction "LFXO_N_V17") (pintype "passive"))
      (node (ref "Y1") (pin "1") (pinfunction "1_1") (pintype "passive"))
    )
    (net (code "67") (name "/LFXO_P") (class "Default")
      (node (ref "C136") (pin "1") (pinfunction "1_1") (pintype "passive"))
      (node (ref "U10") (pin "W17") (pinfunction "LFXO_P_W17") (pintype "input"))
      (node (ref "Y1") (pin "2") (pinfunction "2_2") (pintype "passive"))
    )
    (net (code "68") (name "/MIC_CLK") (class "Default")
      (node (ref "U10") (pin "V5") (pinfunction "P3_6/HFXO_OUT_A_V5") (pintype "bidirectional"))
    )
    (net (code "69") (name "/MIC_DATA") (class "Default")
      (node (ref "U10") (pin "L8") (pinfunction "P3_7/JTAG0_TRACECLK_L8") (pintype "bidirectional"))
    )
    (net (code "70") (name "/MIPI_CSI_CLK_INT_N") (class "Default")
      (node (ref "U10") (pin "V16") (pinfunction "MIPICSI_C_N_V16") (pintype "output"))
    )
    (net (code "71") (name "/MIPI_CSI_CLK_INT_P") (class "Default")
      (node (ref "U10") (pin "W16") (pinfunction "MIPICSI_C_P_W16") (pintype "output"))
    )
    (net (code "72") (name "/MIPI_CSI_D0_INT_N") (class "Default")
      (node (ref "U10") (pin "V14") (pinfunction "MIPICSI_0_N_V14") (pintype "bidirectional"))
    )
    (net (code "73") (name "/MIPI_CSI_D0_INT_P") (class "Default")
      (node (ref "U10") (pin "W14") (pinfunction "MIPICSI_0_P_W14") (pintype "bidirectional"))
    )
    (net (code "74") (name "/MIPI_CSI_D1_INT_N") (class "Default")
      (node (ref "U10") (pin "V15") (pinfunction "MIPICSI_1_N_V15") (pintype "bidirectional"))
    )
    (net (code "75") (name "/MIPI_CSI_D1_INT_P") (class "Default")
      (node (ref "U10") (pin "W15") (pinfunction "MIPICSI_1_P_W15") (pintype "bidirectional"))
    )
    (net (code "76") (name "/MIPI_DSI_CLK_INT_N") (class "Default")
      (node (ref "U10") (pin "V10") (pinfunction "MIPIDSI_C_N_V10") (pintype "output"))
    )
    (net (code "77") (name "/MIPI_DSI_CLK_INT_P") (class "Default")
      (node (ref "U10") (pin "W10") (pinfunction "MIPIDSI_C_P_W10") (pintype "output"))
    )
    (net (code "78") (name "/MIPI_DSI_D0_INT_N") (class "Default")
      (node (ref "U10") (pin "V11") (pinfunction "MIPIDSI_0_N_V11") (pintype "bidirectional"))
    )
    (net (code "79") (name "/MIPI_DSI_D0_INT_P") (class "Default")
      (node (ref "U10") (pin "W11") (pinfunction "MIPIDSI_0_P_W11") (pintype "bidirectional"))
    )
    (net (code "80") (name "/MIPI_DSI_D1_INT_N") (class "Default")
      (node (ref "U10") (pin "V9") (pinfunction "MIPIDSI_1_N_V9") (pintype "bidirectional"))
    )
    (net (code "81") (name "/MIPI_DSI_D1_INT_P") (class "Default")
      (node (ref "U10") (pin "W9") (pinfunction "MIPIDSI_1_P_W9") (pintype "bidirectional"))
    )
    (net (code "82") (name "/MIPI_R") (class "Default")
      (node (ref "R70") (pin "2") (pinfunction "2_2") (pintype "passive"))
      (node (ref "U10") (pin "V13") (pinfunction "MIPI_REXT_V13") (pintype "passive"))
    )
    (net (code "83") (name "/P0_MOSI_INT") (class "Default")
      (node (ref "U10") (pin "B3") (pinfunction "P7_1/SCP1_A_B3") (pintype "bidirectional"))
    )
    (net (code "84") (name "/P1_CAN_TXD_INT") (class "Default")
      (node (ref "U10") (pin "A10") (pinfunction "P12_5_A10") (pintype "bidirectional"))
    )
    (net (code "85") (name "/P1_MISO_INT") (class "Default")
      (node (ref "U10") (pin "B8") (pinfunction "P7_0/SCP0_A_B8") (pintype "bidirectional"))
    )
    (net (code "86") (name "/P2_SCLK_INT") (class "Default")
      (node (ref "U10") (pin "D1") (pinfunction "P7_2/SCP2_A_D1") (pintype "bidirectional"))
    )
    (net (code "87") (name "/P3_CAN_RXD_INT") (class "Default")
      (node (ref "U10") (pin "F5") (pinfunction "P12_4_F5") (pintype "bidirectional"))
    )
    (net (code "88") (name "/P3_SSEL_INT") (class "Default")
      (node (ref "U10") (pin "A8") (pinfunction "P7_3/SCP3_A_A8") (pintype "bidirectional"))
    )
    (net (code "89") (name "/P4_SCL_INT") (class "Default")
      (node (ref "U10") (pin "N15") (pinfunction "P0_5_N15") (pintype "bidirectional"))
    )
    (net (code "90") (name "/P5_SDA_INT") (class "Default")
      (node (ref "U10") (pin "R10") (pinfunction "P0_4_R10") (pintype "bidirectional"))
    )
    (net (code "91") (name "/P6_ADC") (class "Default")
      (node (ref "D20") (pin "1") (pinfunction "1_1") (pintype "bidirectional"))
      (node (ref "Q10") (pin "3") (pinfunction "D_3") (pintype "bidirectional"))
      (node (ref "R57") (pin "1") (pinfunction "1_1") (pintype "passive"))
      (node (ref "R86") (pin "1") (pinfunction "1_1") (pintype "passive"))
    )
    (net (code "92") (name "/P6_ADC_ANALOG") (class "Default")
      (node (ref "R57") (pin "2") (pinfunction "2_2") (pintype "passive"))
      (node (ref "R58") (pin "2") (pinfunction "2_2") (pintype "passive"))
      (node (ref "U10") (pin "J18") (pinfunction "P1_7_J18") (pintype "bidirectional"))
    )
    (net (code "93") (name "/P6_ADC_DIGITAL") (class "Default")
      (node (ref "Q10") (pin "2") (pinfunction "S_2") (pintype "bidirectional"))
      (node (ref "R85") (pin "1") (pinfunction "1_1") (pintype "passive"))
      (node (ref "U10") (pin "B11") (pinfunction "P5_7_B11") (pintype "bidirectional"))
    )
    (net (code "94") (name "/P7_PWM_INT") (class "Default")
      (node (ref "U10") (pin "L15") (pinfunction "P1_2_L15") (pintype "bidirectional"))
    )
    (net (code "95") (name "/P8_PWM_INT") (class "Default")
      (node (ref "U10") (pin "K15") (pinfunction "P1_3_K15") (pintype "bidirectional"))
    )
    (net (code "96") (name "/P9_PWM_INT") (class "Default")
      (node (ref "U10") (pin "E8") (pinfunction "P6_4_E8") (pintype "bidirectional"))
    )
    (net (code "97") (name "/P11_WAKEUP") (class "Default")
      (node (ref "Q5") (pin "3") (pinfunction "D_3") (pintype "bidirectional"))
      (node (ref "R60") (pin "1") (pinfunction "1_1") (pintype "passive"))
    )
    (net (code "98") (name "/P12_RST_N") (class "Default")
      (node (ref "D22") (pin "1") (pinfunction "1_1") (pintype "bidirectional"))
      (node (ref "Q14") (pin "2") (pinfunction "S_2") (pintype "bidirectional"))
      (node (ref "R90") (pin "1") (pinfunction "1_1") (pintype "passive"))
    )
    (net (code "99") (name "/P13_SDA_INT") (class "Default")
      (node (ref "U10") (pin "R14") (pinfunction "P1_0_R14") (pintype "bidirectional"))
    )
    (net (code "100") (name "/P14_SCL_INT") (class "Default")
      (node (ref "U10") (pin "M15") (pinfunction "P1_1_M15") (pintype "bidirectional"))
    )
    (net (code "101") (name "/P15_SSEL_INT") (class "Default")
      (node (ref "U10") (pin "L1") (pinfunction "P9_5_L1") (pintype "bidirectional"))
    )
    (net (code "102") (name "/P16_SCLK_INT") (class "Default")
      (node (ref "U10") (pin "J5") (pinfunction "P9_4_J5") (pintype "bidirectional"))
    )
    (net (code "103") (name "/P17_MISO_INT") (class "Default")
      (node (ref "U10") (pin "G5") (pinfunction "P9_2_G5") (pintype "bidirectional"))
    )
    (net (code "104") (name "/P18_MOSI_INT") (class "Default")
      (node (ref "U10") (pin "H5") (pinfunction "P9_3/HFXO_OUT_B_H5") (pintype "bidirectional"))
    )
    (net (code "105") (name "/PFLASH_CS#") (class "Default")
      (node (ref "U10") (pin "G1") (pinfunction "P14_2_G1") (pintype "bidirectional"))
    )
    (net (code "106") (name "/PFLASH_D0") (class "Default")
      (node (ref "U10") (pin "G18") (pinfunction "P13_0_G18") (pintype "bidirectional"))
    )
    (net (code "107") (name "/PFLASH_D1") (class "Default")
      (node (ref "U10") (pin "G15") (pinfunction "P13_1_G15") (pintype "bidirectional"))
    )
    (net (code "108") (name "/PFLASH_D2") (class "Default")
      (node (ref "U10") (pin "L5") (pinfunction "P9_7_L5") (pintype "bidirectional"))
    )
    (net (code "109") (name "/PFLASH_D3") (class "Default")
      (node (ref "U10") (pin "M2") (pinfunction "P10_0_M2") (pintype "bidirectional"))
    )
    (net (code "110") (name "/PFLASH_D4") (class "Default")
      (node (ref "U10") (pin "M1") (pinfunction "P10_1_M1") (pintype "bidirectional"))
    )
    (net (code "111") (name "/PFLASH_D5") (class "Default")
      (node (ref "U10") (pin "N1") (pinfunction "P10_2_N1") (pintype "bidirectional"))
    )
    (net (code "112") (name "/PFLASH_D6") (class "Default")
      (node (ref "U10") (pin "N2") (pinfunction "P10_3_N2") (pintype "bidirectional"))
    )
    (net (code "113") (name "/PFLASH_D7") (class "Default")
      (node (ref "U10") (pin "M5") (pinfunction "P10_4_M5") (pintype "bidirectional"))
    )
    (net (code "114") (name "/PFLASH_DQSM") (class "Default")
      (node (ref "U10") (pin "P1") (pinfunction "P10_7_P1") (pintype "bidirectional"))
    )
    (net (code "115") (name "/PFLASH_RST#") (class "Default")
      (node (ref "U10") (pin "R7") (pinfunction "P14_3_R7") (pintype "bidirectional"))
    )
    (net (code "116") (name "/PFLASH_SCLK_N") (class "Default")
      (node (ref "U10") (pin "H2") (pinfunction "P14_1_H2") (pintype "bidirectional"))
    )
    (net (code "117") (name "/PFLASH_SCLK_P") (class "Default")
      (node (ref "U10") (pin "B9") (pinfunction "P14_0_B9") (pintype "bidirectional"))
    )
    (net (code "118") (name "/PGOOD") (class "Default")
      (node (ref "U10") (pin "V1") (pinfunction "P15_3_FLEX_V1") (pintype "bidirectional"))
    )
    (net (code "119") (name "/PG_1V8") (class "Default")
      (node (ref "U10") (pin "V2") (pinfunction "P15_0_FLEX_V2") (pintype "bidirectional"))
    )
    (net (code "120") (name "/PMIC_ONOFF") (class "Default")
      (node (ref "Q4") (pin "3") (pinfunction "D_3") (pintype "bidirectional"))
      (node (ref "R59") (pin "1") (pinfunction "1_1") (pintype "passive"))
    )
    (net (code "121") (name "/POWER_SW") (class "Default")
      (node (ref "Q4") (pin "2") (pinfunction "S_2") (pintype "bidirectional"))
      (node (ref "R72") (pin "1") (pinfunction "1_1") (pintype "passive"))
      (node (ref "R73") (pin "1") (pinfunction "1_1") (pintype "passive"))
      (node (ref "S2") (pin "2") (pinfunction "COM_2") (pintype "passive"))
      (node (ref "S2") (pin "3") (pinfunction "COM_3") (pintype "passive"))
      (node (ref "S2") (pin "4") (pinfunction "COM_4") (pintype "passive"))
    )
    (net (code "122") (name "/POWER_SW_INT") (class "Default")
      (node (ref "C137") (pin "2") (pinfunction "2_2") (pintype "passive"))
      (node (ref "R73") (pin "2") (pinfunction "2_2") (pintype "passive"))
      (node (ref "U10") (pin "V4") (pinfunction "P15_6_V4") (pintype "bidirectional"))
    )
    (net (code "123") (name "/PSRAM_CS#") (class "Default")
      (node (ref "U10") (pin "E2") (pinfunction "P3_2_E2") (pintype "bidirectional"))
    )
    (net (code "124") (name "/PSRAM_D0") (class "Default")
      (node (ref "U10") (pin "K19") (pinfunction "P2_0_K19") (pintype "bidirectional"))
    )
    (net (code "125") (name "/PSRAM_D1") (class "Default")
      (node (ref "U10") (pin "K18") (pinfunction "P2_1_K18") (pintype "bidirectional"))
    )
    (net (code "126") (name "/PSRAM_D2") (class "Default")
      (node (ref "U10") (pin "J15") (pinfunction "P2_2_J15") (pintype "bidirectional"))
    )
    (net (code "127") (name "/PSRAM_D3") (class "Default")
      (node (ref "U10") (pin "H15") (pinfunction "P2_3_H15") (pintype "bidirectional"))
    )
    (net (code "128") (name "/PSRAM_D4") (class "Default")
      (node (ref "U10") (pin "G19") (pinfunction "P2_4_G19") (pintype "bidirectional"))
    )
    (net (code "129") (name "/PSRAM_D5") (class "Default")
      (node (ref "U10") (pin "H19") (pinfunction "P2_5_H19") (pintype "bidirectional"))
    )
    (net (code "130") (name "/PSRAM_D6") (class "Default")
      (node (ref "U10") (pin "H18") (pinfunction "P2_6_H18") (pintype "bidirectional"))
    )
    (net (code "131") (name "/PSRAM_D7") (class "Default")
      (node (ref "U10") (pin "J19") (pinfunction "P2_7_J19") (pintype "bidirectional"))
    )
    (net (code "132") (name "/PSRAM_DQSM") (class "Default")
      (node (ref "U10") (pin "L19") (pinfunction "P1_6_L19") (pintype "bidirectional"))
    )
    (net (code "133") (name "/PSRAM_RST#") (class "Default")
      (node (ref "U10") (pin "G2") (pinfunction "P3_3_G2") (pintype "bidirectional"))
    )
    (net (code "134") (name "/PSRAM_SCLK_N") (class "Default")
      (node (ref "U10") (pin "A6") (pinfunction "P3_1_A6") (pintype "bidirectional"))
    )
    (net (code "135") (name "/PSRAM_SCLK_P") (class "Default")
      (node (ref "U10") (pin "B6") (pinfunction "P3_0_B6") (pintype "bidirectional"))
    )
    (net (code "136") (name "/PWM_FSIN_INT") (class "Default")
      (node (ref "U10") (pin "E7") (pinfunction "P6_5_E7") (pintype "bidirectional"))
    )
    (net (code "137") (name "/RST_N") (class "Default")
      (node (ref "C142") (pin "2") (pinfunction "2_2") (pintype "passive"))
      (node (ref "Q13") (pin "2") (pinfunction "S_2") (pintype "bidirectional"))
      (node (ref "R76") (pin "1") (pinfunction "1_1") (pintype "passive"))
      (node (ref "U10") (pin "U18") (pinfunction "POR_N_U18") (pintype "input"))
    )
    (net (code "138") (name "/SD_CD_INT") (class "Default")
      (node (ref "U10") (pin "A15") (pinfunction "P13_7_A15") (pintype "bidirectional"))
    )
    (net (code "139") (name "/SD_CLK_INT") (class "Default")
      (node (ref "U10") (pin "K1") (pinfunction "P9_1_K1") (pintype "bidirectional"))
    )
    (net (code "140") (name "/SD_CMD_INT") (class "Default")
      (node (ref "U10") (pin "K2") (pinfunction "P9_0/JTAG1_TDO_K2") (pintype "bidirectional"))
    )
    (net (code "141") (name "/SD_DAT0_INT") (class "Default")
      (node (ref "U10") (pin "A16") (pinfunction "P5_0_A16") (pintype "bidirectional"))
    )
    (net (code "142") (name "/SD_DAT1_INT") (class "Default")
      (node (ref "U10") (pin "B14") (pinfunction "P5_1_B14") (pintype "bidirectional"))
    )
    (net (code "143") (name "/SD_DAT2_INT") (class "Default")
      (node (ref "U10") (pin "E12") (pinfunction "P5_2_E12") (pintype "bidirectional"))
    )
    (net (code "144") (name "/SD_DAT3_INT") (class "Default")
      (node (ref "U10") (pin "B13") (pinfunction "P5_3_B13") (pintype "bidirectional"))
    )
    (net (code "145") (name "/SD_PWR_INT") (class "Default")
      (node (ref "U10") (pin "A17") (pinfunction "P13_5_A17") (pintype "bidirectional"))
    )
    (net (code "146") (name "/SD_SEL_INT") (class "Default")
      (node (ref "U10") (pin "B15") (pinfunction "P13_6_B15") (pintype "bidirectional"))
    )
    (net (code "147") (name "/SEUART_RX_INT") (class "Default")
      (node (ref "R74") (pin "1") (pinfunction "1_1") (pintype "passive"))
      (node (ref "U10") (pin "A14") (pinfunction "SEUART_RX_A14") (pintype "input"))
    )
    (net (code "148") (name "/SEUART_TX_INT") (class "Default")
      (node (ref "R75") (pin "1") (pinfunction "1_1") (pintype "passive"))
      (node (ref "U10") (pin "A13") (pinfunction "SEUART_TX_A13") (pintype "output"))
    )
    (net (code "149") (name "/ST") (class "Default")
      (node (ref "U10") (pin "W2") (pinfunction "P15_1_FLEX_W2") (pintype "bidirectional"))
    )
    (net (code "150") (name "/TM") (class "Default")
      (node (ref "R78") (pin "1") (pinfunction "1_1") (pintype "passive"))
      (node (ref "U10") (pin "J11") (pinfunction "TEST_MODE_J11") (pintype "input"))
    )
    (net (code "151") (name "/USB_D_N") (class "Default")
      (node (ref "U10") (pin "V7") (pinfunction "USB_DM_V7") (pintype "bidirectional"))
    )
    (net (code "152") (name "/USB_D_P") (class "Default")
      (node (ref "U10") (pin "W7") (pinfunction "USB_DP_W7") (pintype "bidirectional"))
    )
    (net (code "153") (name "/USB_D_SEL_INT") (class "Default")
      (node (ref "U10") (pin "F18") (pinfunction "P4_0/JTAG0_TDATA0_F18") (pintype "bidirectional"))
    )
    (net (code "154") (name "/USB_D_SEL_SBL") (class "Default")
      (node (ref "U10") (pin "B19") (pinfunction "P4_1/JTAG0_TDATA1_B19") (pintype "bidirectional"))
    )
    (net (code "155") (name "/USB_R") (class "Default")
      (node (ref "R71") (pin "1") (pinfunction "1_1") (pintype "passive"))
      (node (ref "U10") (pin "V8") (pinfunction "USB_REXT_V8") (pintype "passive"))
    )
    (net (code "156") (name "/USB_VBUS_R") (class "Default")
      (node (ref "R67") (pin "2") (pinfunction "2_2") (pintype "passive"))
      (node (ref "R69") (pin "1") (pinfunction "1_1") (pintype "passive"))
      (node (ref "U10") (pin "W6") (pinfunction "USB_VBUS_W6") (pintype "input"))
    )
    (net (code "157") (name "/USER_SW_INT") (class "Default")
      (node (ref "C133") (pin "2") (pinfunction "2_2") (pintype "passive"))
      (node (ref "R68") (pin "2") (pinfunction "2_2") (pintype "passive"))
      (node (ref "U10") (pin "W5") (pinfunction "P15_7_W5") (pintype "bidirectional"))
    )
    (net (code "158") (name "/VDD_SX_0V8") (class "Default")
      (node (ref "C128") (pin "1") (pinfunction "1_1") (pintype "passive"))
      (node (ref "C129") (pin "2") (pinfunction "2_2") (pintype "passive"))
      (node (ref "L9") (pin "1") (pinfunction "1_1") (pintype "passive"))
      (node (ref "U10") (pin "A2") (pinfunction "VDD_SX_0V8_A2") (pintype "power_in"))
    )
    (net (code "159") (name "/VREF_P") (class "Default")
      (node (ref "C130") (pin "1") (pinfunction "1_1") (pintype "passive"))
      (node (ref "C131") (pin "2") (pinfunction "2_2") (pintype "passive"))
      (node (ref "U10") (pin "N18") (pinfunction "VREF_P_N18") (pintype "passive"))
    )
    (net (code "160") (name "/VREG_AON") (class "Default")
      (node (ref "R62") (pin "1") (pinfunction "1_1") (pintype "passive"))
      (node (ref "U10") (pin "U17") (pinfunction "VREG_AON_U17") (pintype "power_in"))
    )
    (net (code "161") (name "/VREG_AON_INT") (class "Default")
      (node (ref "C132") (pin "1") (pinfunction "1_1") (pintype "passive"))
      (node (ref "R62") (pin "2") (pinfunction "2_2") (pintype "passive"))
    )
    (net (code "162") (name "/VREG_AUX_1V8") (class "Default")
      (node (ref "C126") (pin "1") (pinfunction "1_1") (pintype "passive"))
      (node (ref "C127") (pin "1") (pinfunction "1_1") (pintype "passive"))
      (node (ref "U10") (pin "V18") (pinfunction "VREG_AUX_1V8_V18") (pintype "power_in"))
    )
    (net (code "163") (name "/VREG_DIG_1V8") (class "Default")
      (node (ref "C124") (pin "1") (pinfunction "1_1") (pintype "passive"))
      (node (ref "C125") (pin "2") (pinfunction "2_2") (pintype "passive"))
      (node (ref "U10") (pin "U19") (pinfunction "VREG_DIG_1V8_U19") (pintype "power_in"))
    )
    (net (code "164") (name "/VREG_LP_1V8") (class "Default")
      (node (ref "C118") (pin "1") (pinfunction "1_1") (pintype "passive"))
      (node (ref "C119") (pin "2") (pinfunction "2_2") (pintype "passive"))
      (node (ref "U10") (pin "W19") (pinfunction "VREG_LP_1V8_W19") (pintype "power_in"))
    )
    (net (code "165") (name "/VREG_MIPI_0V8") (class "Default")
      (node (ref "C122") (pin "1") (pinfunction "1_1") (pintype "passive"))
      (node (ref "C123") (pin "2") (pinfunction "2_2") (pintype "passive"))
      (node (ref "U10") (pin "W13") (pinfunction "VREG_MIPI_0V8_W13") (pintype "power_in"))
    )
    (net (code "166") (name "/VREG_MIPI_1V8") (class "Default")
      (node (ref "C120") (pin "1") (pinfunction "1_1") (pintype "passive"))
      (node (ref "C121") (pin "2") (pinfunction "2_2") (pintype "passive"))
      (node (ref "U10") (pin "N19") (pinfunction "VREG_MIPI_1V8_N19") (pintype "power_in"))
      (node (ref "U10") (pin "W12") (pinfunction "VDD_MIPI_1V8_W12") (pintype "power_in"))
    )
    (net (code "167") (name "/VSW") (class "Default")
      (node (ref "L5") (pin "1") (pinfunction "1_1") (pintype "passive"))
      (node (ref "U10") (pin "T19") (pinfunction "VSW_T19") (pintype "passive"))
    )
    (net (code "168") (name "/WAKEUP_INT") (class "Default")
      (node (ref "Q5") (pin "2") (pinfunction "S_2") (pintype "bidirectional"))
      (node (ref "R61") (pin "1") (pinfunction "1_1") (pintype "passive"))
      (node (ref "U10") (pin "W4") (pinfunction "P15_5_W4") (pintype "bidirectional"))
    )
    (net (code "169") (name "/WIFI_I2S_SCLK") (class "Default")
      (node (ref "U10") (pin "E15") (pinfunction "P12_2_E15") (pintype "bidirectional"))
    )
    (net (code "170") (name "/WIFI_I2S_SDI") (class "Default")
      (node (ref "U10") (pin "F19") (pinfunction "P12_0_F19") (pintype "bidirectional"))
    )
    (net (code "171") (name "/WIFI_I2S_SDO") (class "Default")
      (node (ref "U10") (pin "E18") (pinfunction "P12_1_E18") (pintype "bidirectional"))
    )
    (net (code "172") (name "/WIFI_I2S_WS") (class "Default")
      (node (ref "U10") (pin "D18") (pinfunction "P12_3_D18") (pintype "bidirectional"))
    )
    (net (code "173") (name "/WIFI_IRQ") (class "Default")
      (node (ref "U10") (pin "K5") (pinfunction "P9_6_K5") (pintype "bidirectional"))
    )
    (net (code "174") (name "/WIFI_MISO") (class "Default")
      (node (ref "U10") (pin "N5") (pinfunction "P10_5_N5") (pintype "bidirectional"))
    )
    (net (code "175") (name "/WIFI_MOSI") (class "Default")
      (node (ref "U10") (pin "P5") (pinfunction "P10_6_P5") (pintype "bidirectional"))
    )
    (net (code "176") (name "/WIFI_SCLK") (class "Default")
      (node (ref "U10") (pin "E5") (pinfunction "P12_6_E5") (pintype "bidirectional"))
    )
    (net (code "177") (name "/WIFI_SSEL") (class "Default")
      (node (ref "U10") (pin "D2") (pinfunction "P12_7_D2") (pintype "bidirectional"))
    )
    (net (code "178") (name "/WL_H_WAKE") (class "Default")
      (node (ref "U10") (pin "F15") (pinfunction "P13_2_F15") (pintype "bidirectional"))
    )
    (net (code "179") (name "/WL_REG_ON") (class "Default")
      (node (ref "U10") (pin "C19") (pinfunction "P4_2/JTAG0_TDATA2_C19") (pintype "bidirectional"))
    )
    (net (code "180") (name "GND") (class "Default")
      (node (ref "C102") (pin "1") (pinfunction "1_1") (pintype "passive"))
      (node (ref "C103") (pin "1") (pinfunction "1_1") (pintype "passive"))
      (node (ref "C104") (pin "1") (pinfunction "1_1") (pintype "passive"))
      (node (ref "C105") (pin "1") (pinfunction "1_1") (pintype "passive"))
      (node (ref "C106") (pin "1") (pinfunction "1_1") (pintype "passive"))
      (node (ref "C107") (pin "1") (pinfunction "1_1") (pintype "passive"))
      (node (ref "C108") (pin "2") (pinfunction "2_2") (pintype "passive"))
      (node (ref "C109") (pin "1") (pinfunction "1_1") (pintype "passive"))
      (node (ref "C111") (pin "1") (pinfunction "1_1") (pintype "passive"))
      (node (ref "C112") (pin "2") (pinfunction "2_2") (pintype "passive"))
      (node (ref "C113") (pin "1") (pinfunction "1_1") (pintype "passive"))
      (node (ref "C115") (pin "2") (pinfunction "2_2") (pintype "passive"))
      (node (ref "C117") (pin "1") (pinfunction "1_1") (pintype "passive"))
      (node (ref "C118") (pin "2") (pinfunction "2_2") (pintype "passive"))
      (node (ref "C119") (pin "1") (pinfunction "1_1") (pintype "passive"))
      (node (ref "C120") (pin "2") (pinfunction "2_2") (pintype "passive"))
      (node (ref "C121") (pin "1") (pinfunction "1_1") (pintype "passive"))
      (node (ref "C122") (pin "2") (pinfunction "2_2") (pintype "passive"))
      (node (ref "C123") (pin "1") (pinfunction "1_1") (pintype "passive"))
      (node (ref "C124") (pin "2") (pinfunction "2_2") (pintype "passive"))
      (node (ref "C125") (pin "1") (pinfunction "1_1") (pintype "passive"))
      (node (ref "C126") (pin "2") (pinfunction "2_2") (pintype "passive"))
      (node (ref "C127") (pin "2") (pinfunction "2_2") (pintype "passive"))
      (node (ref "C128") (pin "2") (pinfunction "2_2") (pintype "passive"))
      (node (ref "C129") (pin "1") (pinfunction "1_1") (pintype "passive"))
      (node (ref "C130") (pin "2") (pinfunction "2_2") (pintype "passive"))
      (node (ref "C131") (pin "1") (pinfunction "1_1") (pintype "passive"))
      (node (ref "C132") (pin "2") (pinfunction "2_2") (pintype "passive"))
      (node (ref "C133") (pin "1") (pinfunction "1_1") (pintype "passive"))
      (node (ref "C134") (pin "1") (pinfunction "1_1") (pintype "passive"))
      (node (ref "C135") (pin "1") (pinfunction "1_1") (pintype "passive"))
      (node (ref "C136") (pin "2") (pinfunction "2_2") (pintype "passive"))
      (node (ref "C137") (pin "1") (pinfunction "1_1") (pintype "passive"))
      (node (ref "C138") (pin "2") (pinfunction "2_2") (pintype "passive"))
      (node (ref "C141") (pin "1") (pinfunction "1_1") (pintype "passive"))
      (node (ref "C142") (pin "1") (pinfunction "1_1") (pintype "passive"))
      (node (ref "C143") (pin "1") (pinfunction "1_1") (pintype "passive"))
      (node (ref "C17") (pin "2") (pinfunction "2_2") (pintype "passive"))
      (node (ref "C55") (pin "1") (pinfunction "1_1") (pintype "passive"))
      (node (ref "C56") (pin "1") (pinfunction "1_1") (pintype "passive"))
      (node (ref "C57") (pin "2") (pinfunction "2_2") (pintype "passive"))
      (node (ref "C88") (pin "2") (pinfunction "2_2") (pintype "passive"))
      (node (ref "C91") (pin "1") (pinfunction "1_1") (pintype "passive"))
      (node (ref "C92") (pin "1") (pinfunction "1_1") (pintype "passive"))
      (node (ref "C93") (pin "2") (pinfunction "2_2") (pintype "passive"))
      (node (ref "C94") (pin "1") (pinfunction "1_1") (pintype "passive"))
      (node (ref "C95") (pin "1") (pinfunction "1_1") (pintype "passive"))
      (node (ref "C97") (pin "2") (pinfunction "2_2") (pintype "passive"))
      (node (ref "C98") (pin "1") (pinfunction "1_1") (pintype "passive"))
      (node (ref "C99") (pin "1") (pinfunction "1_1") (pintype "passive"))
      (node (ref "D20") (pin "2") (pinfunction "2_2") (pintype "bidirectional"))
      (node (ref "D21") (pin "2") (pinfunction "2_2") (pintype "bidirectional"))
      (node (ref "D22") (pin "2") (pinfunction "2_2") (pintype "bidirectional"))
      (node (ref "D23") (pin "2") (pinfunction "2_2") (pintype "bidirectional"))
      (node (ref "R58") (pin "1") (pinfunction "1_1") (pintype "passive"))
      (node (ref "R69") (pin "2") (pinfunction "2_2") (pintype "passive"))
      (node (ref "R70") (pin "1") (pinfunction "1_1") (pintype "passive"))
      (node (ref "R71") (pin "2") (pinfunction "2_2") (pintype "passive"))
      (node (ref "R78") (pin "2") (pinfunction "2_2") (pintype "passive"))
      (node (ref "S1") (pin "1") (pinfunction "NO_1") (pintype "passive"))
      (node (ref "S1") (pin "5") (pinfunction "NO_5") (pintype "passive"))
      (node (ref "S2") (pin "1") (pinfunction "NO_1") (pintype "passive"))
      (node (ref "S2") (pin "5") (pinfunction "NO_5") (pintype "passive"))
      (node (ref "U10") (pin "B2") (pinfunction "VSS_B2") (pintype "power_in"))
      (node (ref "U10") (pin "C18") (pinfunction "VSS_C18") (pintype "power_in"))
      (node (ref "U10") (pin "J10") (pinfunction "VSS_J10") (pintype "power_in"))
      (node (ref "U10") (pin "K10") (pinfunction "VSS_K10") (pintype "power_in"))
      (node (ref "U10") (pin "K11") (pinfunction "VSS_K11") (pintype "power_in"))
      (node (ref "U10") (pin "K9") (pinfunction "VSS_K9") (pintype "power_in"))
      (node (ref "U10") (pin "L10") (pinfunction "VSS_L10") (pintype "power_in"))
      (node (ref "U10") (pin "L2") (pinfunction "VSS_L2") (pintype "power_in"))
      (node (ref "U10") (pin "P18") (pinfunction "VSS_ANA_P18") (pintype "power_in"))
      (node (ref "U10") (pin "V12") (pinfunction "VSS_V12") (pintype "power_in"))
      (node (ref "U10") (pin "V19") (pinfunction "VSS_BUCK_V19") (pintype "power_in"))
      (node (ref "X4") (pin "2") (pinfunction "NO_CONNECT_1_2") (pintype "passive"))
      (node (ref "X4") (pin "4") (pinfunction "NO_CONNECT_2_4") (pintype "passive"))
    )
    (net (code "181") (name "Net-(Q13-D)") (class "Default")
      (node (ref "Q13") (pin "3") (pinfunction "D_3") (pintype "bidirectional"))
      (node (ref "Q14") (pin "3") (pinfunction "D_3") (pintype "bidirectional"))
    )
    (net (code "182") (name "Net-(R66-Pad1)") (class "Default")
      (node (ref "R66") (pin "1") (pinfunction "1_1") (pintype "passive"))
      (node (ref "R68") (pin "1") (pinfunction "1_1") (pintype "passive"))
      (node (ref "S1") (pin "2") (pinfunction "COM_2") (pintype "passive"))
      (node (ref "S1") (pin "3") (pinfunction "COM_3") (pintype "passive"))
      (node (ref "S1") (pin "4") (pinfunction "COM_4") (pintype "passive"))
    )
    (net (code "183") (name "RAW") (class "Default")
      (node (ref "R59") (pin "2") (pinfunction "2_2") (pintype "passive"))
      (node (ref "R60") (pin "2") (pinfunction "2_2") (pintype "passive"))
    )
    (net (code "184") (name "VBUS") (class "Default")
      (node (ref "R67") (pin "1") (pinfunction "1_1") (pintype "passive"))
    )
    (net (code "185") (name "VCC_1.8V") (class "Default")
      (node (ref "C107") (pin "2") (pinfunction "2_2") (pintype "passive"))
      (node (ref "C108") (pin "1") (pinfunction "1_1") (pintype "passive"))
      (node (ref "C109") (pin "2") (pinfunction "2_2") (pintype "passive"))
      (node (ref "C111") (pin "2") (pinfunction "2_2") (pintype "passive"))
      (node (ref "C55") (pin "2") (pinfunction "2_2") (pintype "passive"))
      (node (ref "Q13") (pin "1") (pinfunction "G_1") (pintype "bidirectional"))
      (node (ref "Q4") (pin "1") (pinfunction "G_1") (pintype "bidirectional"))
      (node (ref "Q5") (pin "1") (pinfunction "G_1") (pintype "bidirectional"))
      (node (ref "R61") (pin "2") (pinfunction "2_2") (pintype "passive"))
      (node (ref "R66") (pin "2") (pinfunction "2_2") (pintype "passive"))
      (node (ref "R72") (pin "2") (pinfunction "2_2") (pintype "passive"))
      (node (ref "R74") (pin "2") (pinfunction "2_2") (pintype "passive"))
      (node (ref "R75") (pin "2") (pinfunction "2_2") (pintype "passive"))
      (node (ref "R76") (pin "2") (pinfunction "2_2") (pintype "passive"))
      (node (ref "R77") (pin "2") (pinfunction "2_2") (pintype "passive"))
      (node (ref "U10") (pin "A5") (pinfunction "VDD_IO_1V8_A5") (pintype "power_in"))
      (node (ref "U10") (pin "D19") (pinfunction "VDD_IO_1V8_D19") (pintype "power_in"))
      (node (ref "U10") (pin "W3") (pinfunction "VDD_IO_1V8_W3") (pintype "power_in"))
    )
    (net (code "186") (name "VCC_1.8V_GATED") (class "Default")
      (node (ref "Q10") (pin "1") (pinfunction "G_1") (pintype "bidirectional"))
      (node (ref "Q11") (pin "1") (pinfunction "G_1") (pintype "bidirectional"))
      (node (ref "Q12") (pin "1") (pinfunction "G_1") (pintype "bidirectional"))
      (node (ref "Q15") (pin "1") (pinfunction "G_1") (pintype "bidirectional"))
      (node (ref "Q7") (pin "1") (pinfunction "G_1") (pintype "bidirectional"))
      (node (ref "Q8") (pin "1") (pinfunction "G_1") (pintype "bidirectional"))
      (node (ref "Q9") (pin "1") (pinfunction "G_1") (pintype "bidirectional"))
      (node (ref "R83") (pin "2") (pinfunction "2_2") (pintype "passive"))
      (node (ref "R84") (pin "2") (pinfunction "2_2") (pintype "passive"))
      (node (ref "R85") (pin "2") (pinfunction "2_2") (pintype "passive"))
      (node (ref "R87") (pin "2") (pinfunction "2_2") (pintype "passive"))
      (node (ref "R88") (pin "2") (pinfunction "2_2") (pintype "passive"))
      (node (ref "R91") (pin "2") (pinfunction "2_2") (pintype "passive"))
    )
    (net (code "187") (name "VCC_3.3V") (class "Default")
      (node (ref "C112") (pin "1") (pinfunction "1_1") (pintype "passive"))
      (node (ref "C113") (pin "2") (pinfunction "2_2") (pintype "passive"))
      (node (ref "C56") (pin "2") (pinfunction "2_2") (pintype "passive"))
      (node (ref "C57") (pin "1") (pinfunction "1_1") (pintype "passive"))
      (node (ref "C92") (pin "2") (pinfunction "2_2") (pintype "passive"))
      (node (ref "C93") (pin "1") (pinfunction "1_1") (pintype "passive"))
      (node (ref "C94") (pin "2") (pinfunction "2_2") (pintype "passive"))
      (node (ref "C95") (pin "2") (pinfunction "2_2") (pintype "passive"))
      (node (ref "C97") (pin "1") (pinfunction "1_1") (pintype "passive"))
      (node (ref "C98") (pin "2") (pinfunction "2_2") (pintype "passive"))
      (node (ref "C99") (pin "2") (pinfunction "2_2") (pintype "passive"))
      (node (ref "U10") (pin "P19") (pinfunction "VDD_3V3_P19") (pintype "power_in"))
      (node (ref "U10") (pin "R18") (pinfunction "VDD_BUCK_3V3_R18") (pintype "power_in"))
      (node (ref "U10") (pin "W1") (pinfunction "VDD_IO_FLEX_W1") (pintype "power_in"))
      (node (ref "U10") (pin "W8") (pinfunction "VDD_USB_3V3_W8") (pintype "power_in"))
    )
    (net (code "188") (name "VCC_3.3V_CPU") (class "Default")
      (node (ref "C115") (pin "1") (pinfunction "1_1") (pintype "passive"))
      (node (ref "C117") (pin "2") (pinfunction "2_2") (pintype "passive"))
      (node (ref "U10") (pin "T18") (pinfunction "VDD_BATT_T18") (pintype "power_in"))
    )
    (net (code "189") (name "VCC_3.3V_GATED") (class "Default")
      (node (ref "D16") (pin "4") (pinfunction "ANODE_4") (pintype "passive"))
      (node (ref "Q14") (pin "1") (pinfunction "G_1") (pintype "bidirectional"))
      (node (ref "R86") (pin "2") (pinfunction "2_2") (pintype "passive"))
      (node (ref "R89") (pin "2") (pinfunction "2_2") (pintype "passive"))
      (node (ref "R90") (pin "2") (pinfunction "2_2") (pintype "passive"))
      (node (ref "R92") (pin "2") (pinfunction "2_2") (pintype "passive"))
      (node (ref "R97") (pin "2") (pinfunction "2_2") (pintype "passive"))
    )
    (net (code "190") (name "VDD_CORE") (class "Default")
      (node (ref "C102") (pin "2") (pinfunction "2_2") (pintype "passive"))
      (node (ref "C103") (pin "2") (pinfunction "2_2") (pintype "passive"))
      (node (ref "C104") (pin "2") (pinfunction "2_2") (pintype "passive"))
      (node (ref "C105") (pin "2") (pinfunction "2_2") (pintype "passive"))
      (node (ref "C106") (pin "2") (pinfunction "2_2") (pintype "passive"))
      (node (ref "C141") (pin "2") (pinfunction "2_2") (pintype "passive"))
      (node (ref "C17") (pin "1") (pinfunction "1_1") (pintype "passive"))
      (node (ref "C88") (pin "1") (pinfunction "1_1") (pintype "passive"))
      (node (ref "C91") (pin "2") (pinfunction "2_2") (pintype "passive"))
      (node (ref "L5") (pin "2") (pinfunction "2_2") (pintype "passive"))
      (node (ref "L9") (pin "2") (pinfunction "2_2") (pintype "passive"))
      (node (ref "U10") (pin "A1") (pinfunction "VDD_PLL_0V8_A1") (pintype "power_in"))
      (node (ref "U10") (pin "B5") (pinfunction "VDD_CORE_0V8_B5") (pintype "power_in"))
      (node (ref "U10") (pin "E1") (pinfunction "VDD_CORE_0V8_E1") (pintype "power_in"))
      (node (ref "U10") (pin "E19") (pinfunction "VDD_CORE_0V8_E19") (pintype "power_in"))
      (node (ref "U10") (pin "V6") (pinfunction "VDD_CORE_0V8_V6") (pintype "power_in"))
      (node (ref "U10") (pin "W18") (pinfunction "VREG_CORE_0V8_W18") (pintype "power_in"))
    )
    (net (code "191") (name "unconnected-(U10A-nc2-PadB1)") (class "Default")
      (node (ref "U10") (pin "B1") (pinfunction "nc2_B1") (pintype "power_in"))
    )
    (net (code "192") (name "unconnected-(U10B-AMUX_P-PadJ8)") (class "Default")
      (node (ref "U10") (pin "J8") (pinfunction "AMUX_P_J8") (pintype "passive"))
    )
    (net (code "193") (name "unconnected-(U10B-AMUX_PMU-PadM18)") (class "Default")
      (node (ref "U10") (pin "M18") (pinfunction "AMUX_PMU_M18") (pintype "passive"))
    )
    (net (code "194") (name "unconnected-(U10B-nc3-PadC1)") (class "Default")
      (node (ref "U10") (pin "C1") (pinfunction "nc3_C1") (pintype "input"))
    )
    (net (code "195") (name "unconnected-(U10D-USB_IO_ID-PadR9)") (class "Default")
      (node (ref "U10") (pin "R9") (pinfunction "USB_IO_ID_R9") (pintype "input"))
    )
  )
)
